# LED_INDICATORS.net
KiCad netlist of a schematic drawn in Altium Designer
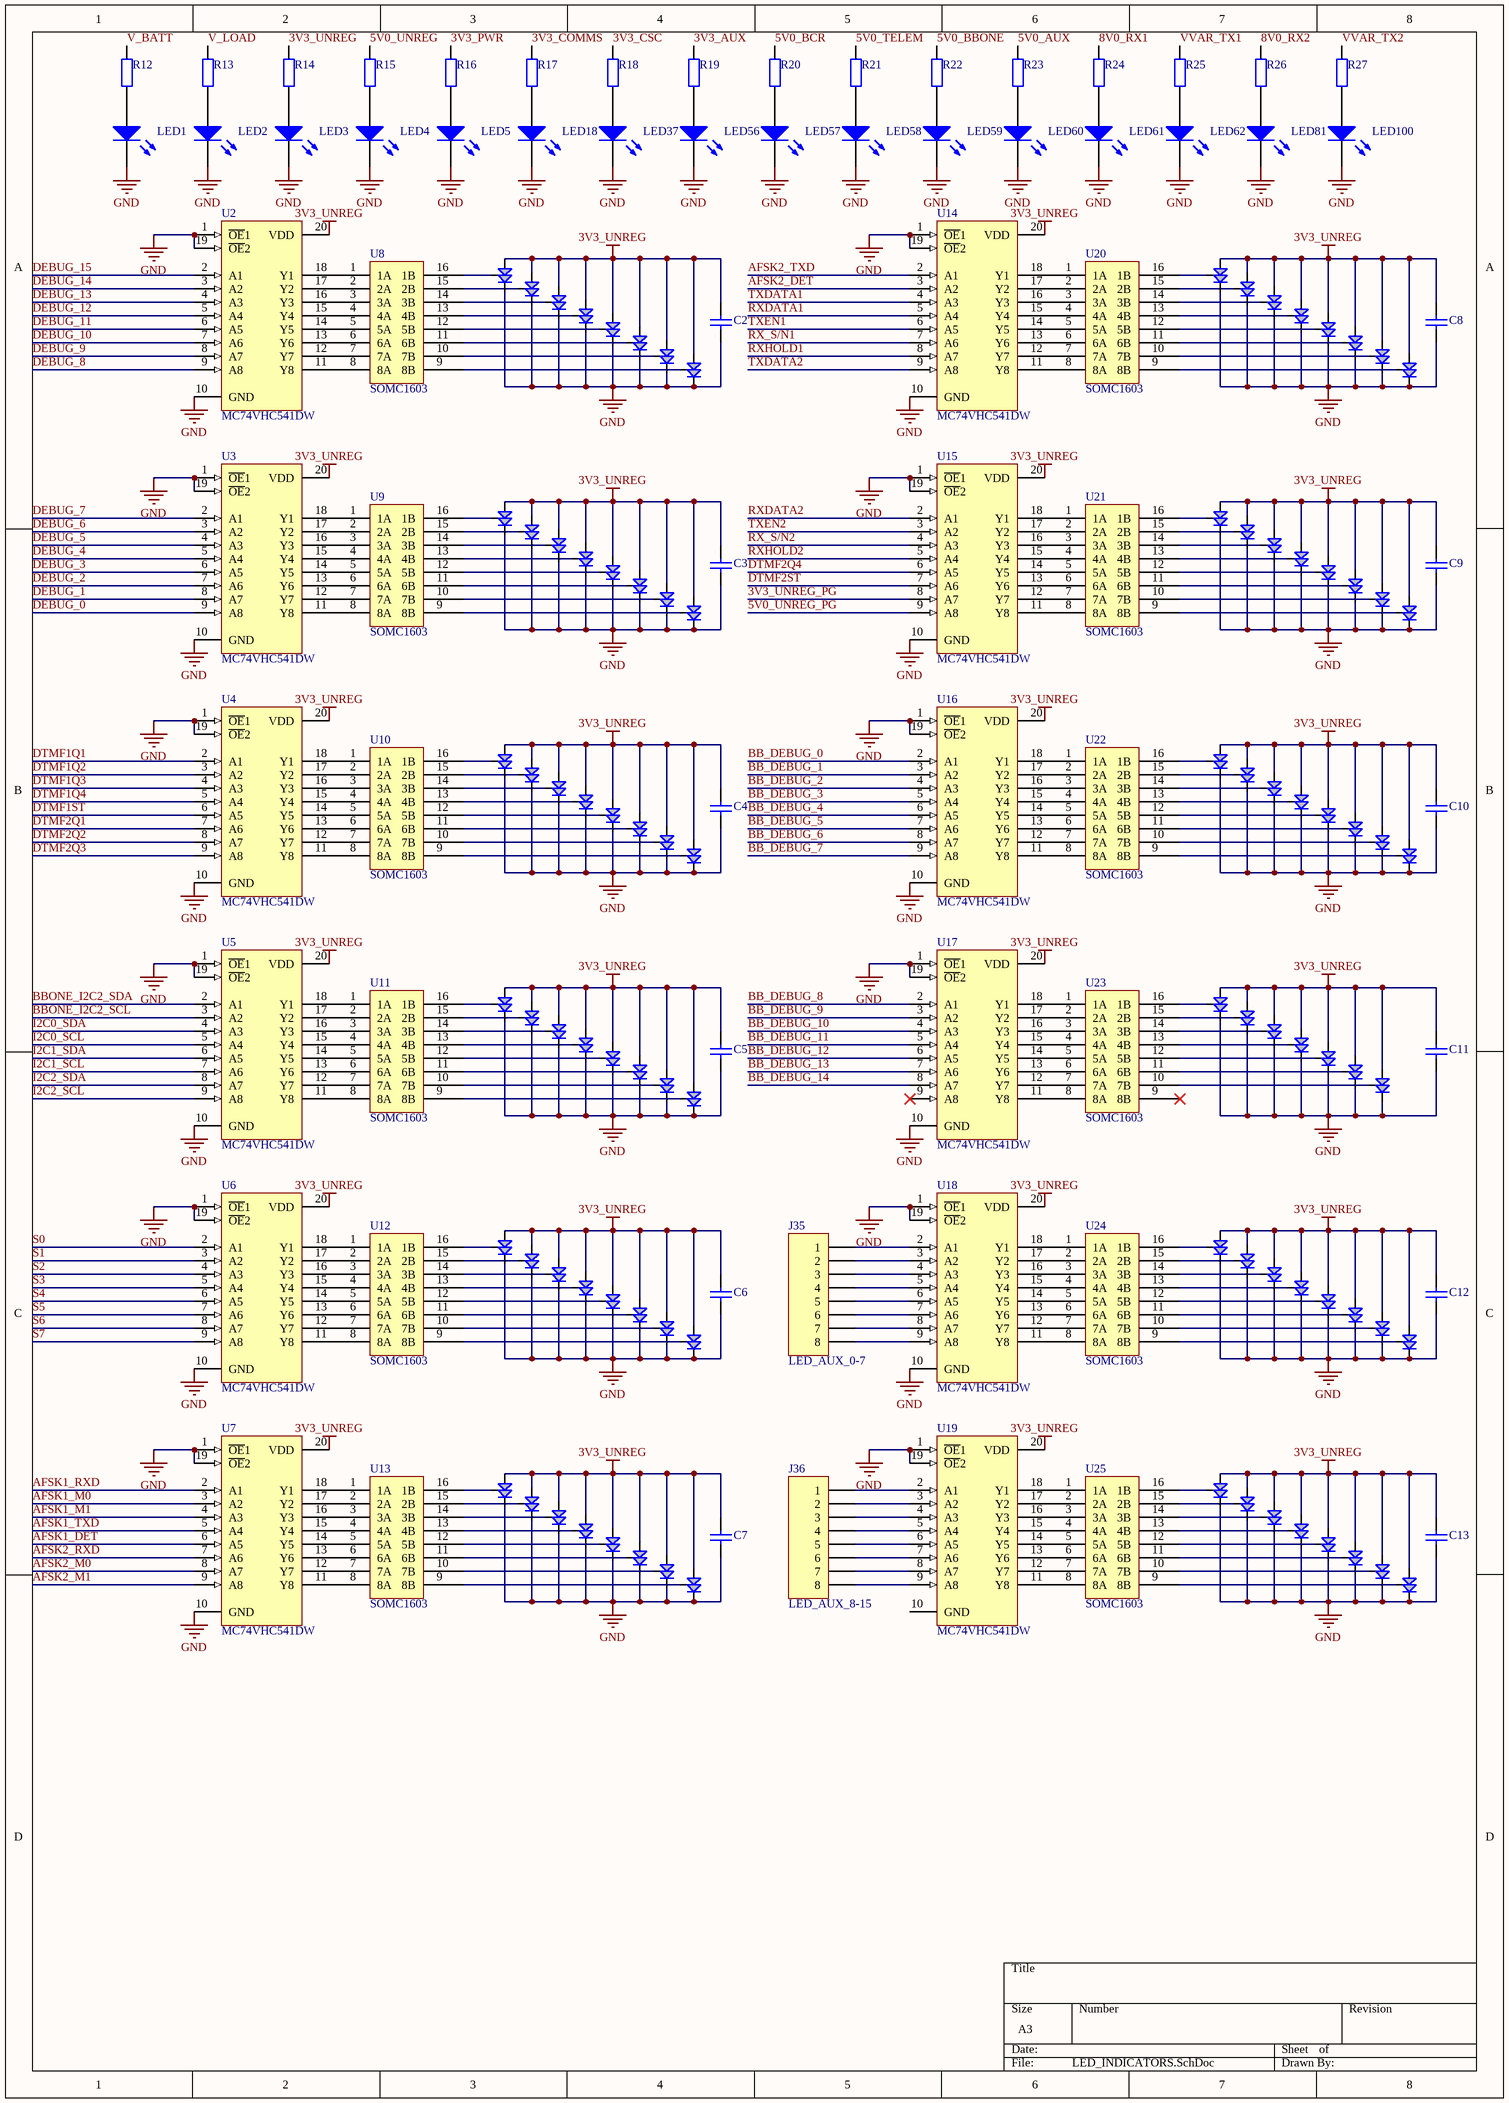
[diagram p0: LED_INDICATORS.SchDoc]

(export (version "E")
  (design (tool "Eeschema 10.0.6"))
  (components
    (comp (ref "C2")
      (value "~")
      (footprint "6-0805_M")
      (description "Capacitor")
      (fields (field (name "PUBLISHER") "Altium Limited"))
      (libsource (lib "Miscellaneous Devices") (part "Cap"))
    )
    (comp (ref "C3")
      (value "~")
      (footprint "6-0805_M")
      (description "Capacitor")
      (fields (field (name "PUBLISHER") "Altium Limited"))
      (libsource (lib "Miscellaneous Devices") (part "Cap"))
    )
    (comp (ref "C4")
      (value "~")
      (footprint "6-0805_M")
      (description "Capacitor")
      (fields (field (name "PUBLISHER") "Altium Limited"))
      (libsource (lib "Miscellaneous Devices") (part "Cap"))
    )
    (comp (ref "C5")
      (value "~")
      (footprint "6-0805_M")
      (description "Capacitor")
      (fields (field (name "PUBLISHER") "Altium Limited"))
      (libsource (lib "Miscellaneous Devices") (part "Cap"))
    )
    (comp (ref "C6")
      (value "~")
      (footprint "6-0805_M")
      (description "Capacitor")
      (fields (field (name "PUBLISHER") "Altium Limited"))
      (libsource (lib "Miscellaneous Devices") (part "Cap"))
    )
    (comp (ref "C7")
      (value "~")
      (footprint "6-0805_M")
      (description "Capacitor")
      (fields (field (name "PUBLISHER") "Altium Limited"))
      (libsource (lib "Miscellaneous Devices") (part "Cap"))
    )
    (comp (ref "C8")
      (value "~")
      (footprint "6-0805_M")
      (description "Capacitor")
      (fields (field (name "PUBLISHER") "Altium Limited"))
      (libsource (lib "Miscellaneous Devices") (part "Cap"))
    )
    (comp (ref "C9")
      (value "~")
      (footprint "6-0805_M")
      (description "Capacitor")
      (fields (field (name "PUBLISHER") "Altium Limited"))
      (libsource (lib "Miscellaneous Devices") (part "Cap"))
    )
    (comp (ref "C10")
      (value "~")
      (footprint "6-0805_M")
      (description "Capacitor")
      (fields (field (name "PUBLISHER") "Altium Limited"))
      (libsource (lib "Miscellaneous Devices") (part "Cap"))
    )
    (comp (ref "C11")
      (value "~")
      (footprint "6-0805_M")
      (description "Capacitor")
      (fields (field (name "PUBLISHER") "Altium Limited"))
      (libsource (lib "Miscellaneous Devices") (part "Cap"))
    )
    (comp (ref "C12")
      (value "~")
      (footprint "6-0805_M")
      (description "Capacitor")
      (fields (field (name "PUBLISHER") "Altium Limited"))
      (libsource (lib "Miscellaneous Devices") (part "Cap"))
    )
    (comp (ref "C13")
      (value "~")
      (footprint "6-0805_M")
      (description "Capacitor")
      (fields (field (name "PUBLISHER") "Altium Limited"))
      (libsource (lib "Miscellaneous Devices") (part "Cap"))
    )
    (comp (ref "J35")
      (value "LED_AUX_0-7")
      (footprint "HDR1X8")
      (description "Header, 8-Pin")
      (fields (field (name "PUBLISHER") "Altium Limited"))
      (libsource (lib "Miscellaneous Connectors") (part "Header 8"))
    )
    (comp (ref "J36")
      (value "LED_AUX_8-15")
      (footprint "HDR1X8")
      (description "Header, 8-Pin")
      (fields (field (name "PUBLISHER") "Altium Limited"))
      (libsource (lib "Miscellaneous Connectors") (part "Header 8"))
    )
    (comp (ref "LED1")
      (value "V_BATT")
      (footprint "6-0805_M")
      (description "Typical INFRARED GaAs LED")
      (fields (field (name "PUBLISHER") "Altium Limited"))
      (libsource (lib "Miscellaneous Devices") (part "LED0"))
    )
    (comp (ref "LED2")
      (value "V_LOAD")
      (footprint "6-0805_M")
      (description "Typical INFRARED GaAs LED")
      (fields (field (name "PUBLISHER") "Altium Limited"))
      (libsource (lib "Miscellaneous Devices") (part "LED0"))
    )
    (comp (ref "LED3")
      (value "3V3_UNREG")
      (footprint "6-0805_M")
      (description "Typical INFRARED GaAs LED")
      (fields (field (name "PUBLISHER") "Altium Limited"))
      (libsource (lib "Miscellaneous Devices") (part "LED0"))
    )
    (comp (ref "LED4")
      (value "5V0_UNREG")
      (footprint "6-0805_M")
      (description "Typical INFRARED GaAs LED")
      (fields (field (name "PUBLISHER") "Altium Limited"))
      (libsource (lib "Miscellaneous Devices") (part "LED0"))
    )
    (comp (ref "LED5")
      (value "3V3_PWR")
      (footprint "6-0805_M")
      (description "Typical INFRARED GaAs LED")
      (fields (field (name "PUBLISHER") "Altium Limited"))
      (libsource (lib "Miscellaneous Devices") (part "LED0"))
    )
    (comp (ref "LED6")
      (value "DEBUG_15")
      (footprint "BIDIRECTIONAL LED")
      (libsource (lib "FlatBoards") (part "BIDIRECTIONAL LED"))
    )
    (comp (ref "LED7")
      (value "DEBUG_7")
      (footprint "BIDIRECTIONAL LED")
      (libsource (lib "FlatBoards") (part "BIDIRECTIONAL LED"))
    )
    (comp (ref "LED8")
      (value "DTMF1Q1")
      (footprint "BIDIRECTIONAL LED")
      (libsource (lib "FlatBoards") (part "BIDIRECTIONAL LED"))
    )
    (comp (ref "LED9")
      (value "DTMF2Q4")
      (footprint "BIDIRECTIONAL LED")
      (libsource (lib "FlatBoards") (part "BIDIRECTIONAL LED"))
    )
    (comp (ref "LED10")
      (value "S0")
      (footprint "BIDIRECTIONAL LED")
      (libsource (lib "FlatBoards") (part "BIDIRECTIONAL LED"))
    )
    (comp (ref "LED11")
      (value "AFSK1_RXD")
      (footprint "BIDIRECTIONAL LED")
      (libsource (lib "FlatBoards") (part "BIDIRECTIONAL LED"))
    )
    (comp (ref "LED12")
      (value "DEBUG_14")
      (footprint "BIDIRECTIONAL LED")
      (libsource (lib "FlatBoards") (part "BIDIRECTIONAL LED"))
    )
    (comp (ref "LED13")
      (value "DEBUG_6")
      (footprint "BIDIRECTIONAL LED")
      (libsource (lib "FlatBoards") (part "BIDIRECTIONAL LED"))
    )
    (comp (ref "LED14")
      (value "DTMF1Q2")
      (footprint "BIDIRECTIONAL LED")
      (libsource (lib "FlatBoards") (part "BIDIRECTIONAL LED"))
    )
    (comp (ref "LED15")
      (value "DTMF2ST")
      (footprint "BIDIRECTIONAL LED")
      (libsource (lib "FlatBoards") (part "BIDIRECTIONAL LED"))
    )
    (comp (ref "LED16")
      (value "S1")
      (footprint "BIDIRECTIONAL LED")
      (libsource (lib "FlatBoards") (part "BIDIRECTIONAL LED"))
    )
    (comp (ref "LED17")
      (value "AFSK1_M0")
      (footprint "BIDIRECTIONAL LED")
      (libsource (lib "FlatBoards") (part "BIDIRECTIONAL LED"))
    )
    (comp (ref "LED18")
      (value "3V3_COMMS")
      (footprint "6-0805_M")
      (description "Typical INFRARED GaAs LED")
      (fields (field (name "PUBLISHER") "Altium Limited"))
      (libsource (lib "Miscellaneous Devices") (part "LED0"))
    )
    (comp (ref "LED19")
      (value "DEBUG_13")
      (footprint "BIDIRECTIONAL LED")
      (libsource (lib "FlatBoards") (part "BIDIRECTIONAL LED"))
    )
    (comp (ref "LED20")
      (value "DEBUG_5")
      (footprint "BIDIRECTIONAL LED")
      (libsource (lib "FlatBoards") (part "BIDIRECTIONAL LED"))
    )
    (comp (ref "LED21")
      (value "DTMF1Q3")
      (footprint "BIDIRECTIONAL LED")
      (libsource (lib "FlatBoards") (part "BIDIRECTIONAL LED"))
    )
    (comp (ref "LED22")
      (value "I2C0_SDA")
      (footprint "BIDIRECTIONAL LED")
      (libsource (lib "FlatBoards") (part "BIDIRECTIONAL LED"))
    )
    (comp (ref "LED23")
      (value "S2")
      (footprint "BIDIRECTIONAL LED")
      (libsource (lib "FlatBoards") (part "BIDIRECTIONAL LED"))
    )
    (comp (ref "LED24")
      (value "AFSK1_M1")
      (footprint "BIDIRECTIONAL LED")
      (libsource (lib "FlatBoards") (part "BIDIRECTIONAL LED"))
    )
    (comp (ref "LED25")
      (value "DEBUG_12")
      (footprint "BIDIRECTIONAL LED")
      (libsource (lib "FlatBoards") (part "BIDIRECTIONAL LED"))
    )
    (comp (ref "LED26")
      (value "DEBUG_4")
      (footprint "BIDIRECTIONAL LED")
      (libsource (lib "FlatBoards") (part "BIDIRECTIONAL LED"))
    )
    (comp (ref "LED27")
      (value "DTMF1Q4")
      (footprint "BIDIRECTIONAL LED")
      (libsource (lib "FlatBoards") (part "BIDIRECTIONAL LED"))
    )
    (comp (ref "LED28")
      (value "I2C0_SCL")
      (footprint "BIDIRECTIONAL LED")
      (libsource (lib "FlatBoards") (part "BIDIRECTIONAL LED"))
    )
    (comp (ref "LED29")
      (value "S3")
      (footprint "BIDIRECTIONAL LED")
      (libsource (lib "FlatBoards") (part "BIDIRECTIONAL LED"))
    )
    (comp (ref "LED30")
      (value "AFSK1_TXD")
      (footprint "BIDIRECTIONAL LED")
      (libsource (lib "FlatBoards") (part "BIDIRECTIONAL LED"))
    )
    (comp (ref "LED31")
      (value "DEBUG_11")
      (footprint "BIDIRECTIONAL LED")
      (libsource (lib "FlatBoards") (part "BIDIRECTIONAL LED"))
    )
    (comp (ref "LED32")
      (value "DEBUG_3")
      (footprint "BIDIRECTIONAL LED")
      (libsource (lib "FlatBoards") (part "BIDIRECTIONAL LED"))
    )
    (comp (ref "LED33")
      (value "DTMF1ST")
      (footprint "BIDIRECTIONAL LED")
      (libsource (lib "FlatBoards") (part "BIDIRECTIONAL LED"))
    )
    (comp (ref "LED34")
      (value "I2C1_SDA")
      (footprint "BIDIRECTIONAL LED")
      (libsource (lib "FlatBoards") (part "BIDIRECTIONAL LED"))
    )
    (comp (ref "LED35")
      (value "S4")
      (footprint "BIDIRECTIONAL LED")
      (libsource (lib "FlatBoards") (part "BIDIRECTIONAL LED"))
    )
    (comp (ref "LED36")
      (value "AFSK1_DET")
      (footprint "BIDIRECTIONAL LED")
      (libsource (lib "FlatBoards") (part "BIDIRECTIONAL LED"))
    )
    (comp (ref "LED37")
      (value "3V3_CSC")
      (footprint "6-0805_M")
      (description "Typical INFRARED GaAs LED")
      (fields (field (name "PUBLISHER") "Altium Limited"))
      (libsource (lib "Miscellaneous Devices") (part "LED0"))
    )
    (comp (ref "LED38")
      (value "DEBUG_10")
      (footprint "BIDIRECTIONAL LED")
      (libsource (lib "FlatBoards") (part "BIDIRECTIONAL LED"))
    )
    (comp (ref "LED39")
      (value "DEBUG_2")
      (footprint "BIDIRECTIONAL LED")
      (libsource (lib "FlatBoards") (part "BIDIRECTIONAL LED"))
    )
    (comp (ref "LED40")
      (value "DTMF2Q1")
      (footprint "BIDIRECTIONAL LED")
      (libsource (lib "FlatBoards") (part "BIDIRECTIONAL LED"))
    )
    (comp (ref "LED41")
      (value "I2C1_SCL")
      (footprint "BIDIRECTIONAL LED")
      (libsource (lib "FlatBoards") (part "BIDIRECTIONAL LED"))
    )
    (comp (ref "LED42")
      (value "S5")
      (footprint "BIDIRECTIONAL LED")
      (libsource (lib "FlatBoards") (part "BIDIRECTIONAL LED"))
    )
    (comp (ref "LED43")
      (value "AFSK2_RXD")
      (footprint "BIDIRECTIONAL LED")
      (libsource (lib "FlatBoards") (part "BIDIRECTIONAL LED"))
    )
    (comp (ref "LED44")
      (value "DEBUG_9")
      (footprint "BIDIRECTIONAL LED")
      (libsource (lib "FlatBoards") (part "BIDIRECTIONAL LED"))
    )
    (comp (ref "LED45")
      (value "DEBUG_1")
      (footprint "BIDIRECTIONAL LED")
      (libsource (lib "FlatBoards") (part "BIDIRECTIONAL LED"))
    )
    (comp (ref "LED46")
      (value "DTMF2Q2")
      (footprint "BIDIRECTIONAL LED")
      (libsource (lib "FlatBoards") (part "BIDIRECTIONAL LED"))
    )
    (comp (ref "LED47")
      (value "I2C2_SDA")
      (footprint "BIDIRECTIONAL LED")
      (libsource (lib "FlatBoards") (part "BIDIRECTIONAL LED"))
    )
    (comp (ref "LED48")
      (value "S6")
      (footprint "BIDIRECTIONAL LED")
      (libsource (lib "FlatBoards") (part "BIDIRECTIONAL LED"))
    )
    (comp (ref "LED49")
      (value "AFSK2_M0")
      (footprint "BIDIRECTIONAL LED")
      (libsource (lib "FlatBoards") (part "BIDIRECTIONAL LED"))
    )
    (comp (ref "LED50")
      (value "DEBUG_8")
      (footprint "BIDIRECTIONAL LED")
      (libsource (lib "FlatBoards") (part "BIDIRECTIONAL LED"))
    )
    (comp (ref "LED51")
      (value "DEBUG_0")
      (footprint "BIDIRECTIONAL LED")
      (libsource (lib "FlatBoards") (part "BIDIRECTIONAL LED"))
    )
    (comp (ref "LED52")
      (value "DTMF2Q3")
      (footprint "BIDIRECTIONAL LED")
      (libsource (lib "FlatBoards") (part "BIDIRECTIONAL LED"))
    )
    (comp (ref "LED53")
      (value "I2C2_SCL")
      (footprint "BIDIRECTIONAL LED")
      (libsource (lib "FlatBoards") (part "BIDIRECTIONAL LED"))
    )
    (comp (ref "LED54")
      (value "S7")
      (footprint "BIDIRECTIONAL LED")
      (libsource (lib "FlatBoards") (part "BIDIRECTIONAL LED"))
    )
    (comp (ref "LED55")
      (value "AFSK2_M1")
      (footprint "BIDIRECTIONAL LED")
      (libsource (lib "FlatBoards") (part "BIDIRECTIONAL LED"))
    )
    (comp (ref "LED56")
      (value "3V3_AUX")
      (footprint "6-0805_M")
      (description "Typical INFRARED GaAs LED")
      (fields (field (name "PUBLISHER") "Altium Limited"))
      (libsource (lib "Miscellaneous Devices") (part "LED0"))
    )
    (comp (ref "LED57")
      (value "5V0_BCR")
      (footprint "6-0805_M")
      (description "Typical INFRARED GaAs LED")
      (fields (field (name "PUBLISHER") "Altium Limited"))
      (libsource (lib "Miscellaneous Devices") (part "LED0"))
    )
    (comp (ref "LED58")
      (value "5V0_TELEM")
      (footprint "6-0805_M")
      (description "Typical INFRARED GaAs LED")
      (fields (field (name "PUBLISHER") "Altium Limited"))
      (libsource (lib "Miscellaneous Devices") (part "LED0"))
    )
    (comp (ref "LED59")
      (value "5V0_BBONE")
      (footprint "6-0805_M")
      (description "Typical INFRARED GaAs LED")
      (fields (field (name "PUBLISHER") "Altium Limited"))
      (libsource (lib "Miscellaneous Devices") (part "LED0"))
    )
    (comp (ref "LED60")
      (value "5V0_AUX")
      (footprint "6-0805_M")
      (description "Typical INFRARED GaAs LED")
      (fields (field (name "PUBLISHER") "Altium Limited"))
      (libsource (lib "Miscellaneous Devices") (part "LED0"))
    )
    (comp (ref "LED61")
      (value "8V0_RX1")
      (footprint "6-0805_M")
      (description "Typical INFRARED GaAs LED")
      (fields (field (name "PUBLISHER") "Altium Limited"))
      (libsource (lib "Miscellaneous Devices") (part "LED0"))
    )
    (comp (ref "LED62")
      (value "VVAR_TX1")
      (footprint "6-0805_M")
      (description "Typical INFRARED GaAs LED")
      (fields (field (name "PUBLISHER") "Altium Limited"))
      (libsource (lib "Miscellaneous Devices") (part "LED0"))
    )
    (comp (ref "LED63")
      (value "AFSK2_TXD")
      (footprint "BIDIRECTIONAL LED")
      (libsource (lib "FlatBoards") (part "BIDIRECTIONAL LED"))
    )
    (comp (ref "LED64")
      (value "RXDATA2")
      (footprint "BIDIRECTIONAL LED")
      (libsource (lib "FlatBoards") (part "BIDIRECTIONAL LED"))
    )
    (comp (ref "LED65")
      (value "BB_DEBUG_0")
      (footprint "BIDIRECTIONAL LED")
      (libsource (lib "FlatBoards") (part "BIDIRECTIONAL LED"))
    )
    (comp (ref "LED66")
      (value "BB_DEBUG_8")
      (footprint "BIDIRECTIONAL LED")
      (libsource (lib "FlatBoards") (part "BIDIRECTIONAL LED"))
    )
    (comp (ref "LED67")
      (value "LED_AUX_0")
      (footprint "BIDIRECTIONAL LED")
      (libsource (lib "FlatBoards") (part "BIDIRECTIONAL LED"))
    )
    (comp (ref "LED68")
      (value "LED_AUX_8")
      (footprint "BIDIRECTIONAL LED")
      (libsource (lib "FlatBoards") (part "BIDIRECTIONAL LED"))
    )
    (comp (ref "LED69")
      (value "AFSK2_DET")
      (footprint "BIDIRECTIONAL LED")
      (libsource (lib "FlatBoards") (part "BIDIRECTIONAL LED"))
    )
    (comp (ref "LED70")
      (value "TXEN2")
      (footprint "BIDIRECTIONAL LED")
      (libsource (lib "FlatBoards") (part "BIDIRECTIONAL LED"))
    )
    (comp (ref "LED71")
      (value "BB_DEBUG_1")
      (footprint "BIDIRECTIONAL LED")
      (libsource (lib "FlatBoards") (part "BIDIRECTIONAL LED"))
    )
    (comp (ref "LED72")
      (value "BB_DEBUG_9")
      (footprint "BIDIRECTIONAL LED")
      (libsource (lib "FlatBoards") (part "BIDIRECTIONAL LED"))
    )
    (comp (ref "LED73")
      (value "LED_AUX_1")
      (footprint "BIDIRECTIONAL LED")
      (libsource (lib "FlatBoards") (part "BIDIRECTIONAL LED"))
    )
    (comp (ref "LED74")
      (value "LED_AUX_9")
      (footprint "BIDIRECTIONAL LED")
      (libsource (lib "FlatBoards") (part "BIDIRECTIONAL LED"))
    )
    (comp (ref "LED75")
      (value "TXDATA1")
      (footprint "BIDIRECTIONAL LED")
      (libsource (lib "FlatBoards") (part "BIDIRECTIONAL LED"))
    )
    (comp (ref "LED76")
      (value "RX_S/N2")
      (footprint "BIDIRECTIONAL LED")
      (libsource (lib "FlatBoards") (part "BIDIRECTIONAL LED"))
    )
    (comp (ref "LED77")
      (value "BB_DEBUG_2")
      (footprint "BIDIRECTIONAL LED")
      (libsource (lib "FlatBoards") (part "BIDIRECTIONAL LED"))
    )
    (comp (ref "LED78")
      (value "BB_DEBUG_10")
      (footprint "BIDIRECTIONAL LED")
      (libsource (lib "FlatBoards") (part "BIDIRECTIONAL LED"))
    )
    (comp (ref "LED79")
      (value "LED_AUX_2")
      (footprint "BIDIRECTIONAL LED")
      (libsource (lib "FlatBoards") (part "BIDIRECTIONAL LED"))
    )
    (comp (ref "LED80")
      (value "LED_AUX_10")
      (footprint "BIDIRECTIONAL LED")
      (libsource (lib "FlatBoards") (part "BIDIRECTIONAL LED"))
    )
    (comp (ref "LED81")
      (value "8V0_RX2")
      (footprint "6-0805_M")
      (description "Typical INFRARED GaAs LED")
      (fields (field (name "PUBLISHER") "Altium Limited"))
      (libsource (lib "Miscellaneous Devices") (part "LED0"))
    )
    (comp (ref "LED82")
      (value "RXDATA1")
      (footprint "BIDIRECTIONAL LED")
      (libsource (lib "FlatBoards") (part "BIDIRECTIONAL LED"))
    )
    (comp (ref "LED83")
      (value "RXHOLD2")
      (footprint "BIDIRECTIONAL LED")
      (libsource (lib "FlatBoards") (part "BIDIRECTIONAL LED"))
    )
    (comp (ref "LED84")
      (value "BB_DEBUG_3")
      (footprint "BIDIRECTIONAL LED")
      (libsource (lib "FlatBoards") (part "BIDIRECTIONAL LED"))
    )
    (comp (ref "LED85")
      (value "BB_DEBUG_11")
      (footprint "BIDIRECTIONAL LED")
      (libsource (lib "FlatBoards") (part "BIDIRECTIONAL LED"))
    )
    (comp (ref "LED86")
      (value "LED_AUX_3")
      (footprint "BIDIRECTIONAL LED")
      (libsource (lib "FlatBoards") (part "BIDIRECTIONAL LED"))
    )
    (comp (ref "LED87")
      (value "LED_AUX_11")
      (footprint "BIDIRECTIONAL LED")
      (libsource (lib "FlatBoards") (part "BIDIRECTIONAL LED"))
    )
    (comp (ref "LED88")
      (value "TXEN1")
      (footprint "BIDIRECTIONAL LED")
      (libsource (lib "FlatBoards") (part "BIDIRECTIONAL LED"))
    )
    (comp (ref "LED89")
      (value "BBONE_I2C2_SDA")
      (footprint "BIDIRECTIONAL LED")
      (libsource (lib "FlatBoards") (part "BIDIRECTIONAL LED"))
    )
    (comp (ref "LED90")
      (value "BB_DEBUG_4")
      (footprint "BIDIRECTIONAL LED")
      (libsource (lib "FlatBoards") (part "BIDIRECTIONAL LED"))
    )
    (comp (ref "LED91")
      (value "BB_DEBUG_12")
      (footprint "BIDIRECTIONAL LED")
      (libsource (lib "FlatBoards") (part "BIDIRECTIONAL LED"))
    )
    (comp (ref "LED92")
      (value "LED_AUX_4")
      (footprint "BIDIRECTIONAL LED")
      (libsource (lib "FlatBoards") (part "BIDIRECTIONAL LED"))
    )
    (comp (ref "LED93")
      (value "LED_AUX_12")
      (footprint "BIDIRECTIONAL LED")
      (libsource (lib "FlatBoards") (part "BIDIRECTIONAL LED"))
    )
    (comp (ref "LED94")
      (value "RX_S/N1")
      (footprint "BIDIRECTIONAL LED")
      (libsource (lib "FlatBoards") (part "BIDIRECTIONAL LED"))
    )
    (comp (ref "LED95")
      (value "BBONE_I2C2_SCL")
      (footprint "BIDIRECTIONAL LED")
      (libsource (lib "FlatBoards") (part "BIDIRECTIONAL LED"))
    )
    (comp (ref "LED96")
      (value "BB_DEBUG_5")
      (footprint "BIDIRECTIONAL LED")
      (libsource (lib "FlatBoards") (part "BIDIRECTIONAL LED"))
    )
    (comp (ref "LED97")
      (value "BB_DEBUG_13")
      (footprint "BIDIRECTIONAL LED")
      (libsource (lib "FlatBoards") (part "BIDIRECTIONAL LED"))
    )
    (comp (ref "LED98")
      (value "LED_AUX_5")
      (footprint "BIDIRECTIONAL LED")
      (libsource (lib "FlatBoards") (part "BIDIRECTIONAL LED"))
    )
    (comp (ref "LED99")
      (value "LED_AUX_13")
      (footprint "BIDIRECTIONAL LED")
      (libsource (lib "FlatBoards") (part "BIDIRECTIONAL LED"))
    )
    (comp (ref "LED100")
      (value "VVAR_TX2")
      (footprint "6-0805_M")
      (description "Typical INFRARED GaAs LED")
      (fields (field (name "PUBLISHER") "Altium Limited"))
      (libsource (lib "Miscellaneous Devices") (part "LED0"))
    )
    (comp (ref "LED101")
      (value "RXHOLD1")
      (footprint "BIDIRECTIONAL LED")
      (libsource (lib "FlatBoards") (part "BIDIRECTIONAL LED"))
    )
    (comp (ref "LED102")
      (value "3V3_UNREG_PG")
      (footprint "BIDIRECTIONAL LED")
      (libsource (lib "FlatBoards") (part "BIDIRECTIONAL LED"))
    )
    (comp (ref "LED103")
      (value "BB_DEBUG_6")
      (footprint "BIDIRECTIONAL LED")
      (libsource (lib "FlatBoards") (part "BIDIRECTIONAL LED"))
    )
    (comp (ref "LED104")
      (value "BB_DEBUG_14")
      (footprint "BIDIRECTIONAL LED")
      (libsource (lib "FlatBoards") (part "BIDIRECTIONAL LED"))
    )
    (comp (ref "LED105")
      (value "LED_AUX_6")
      (footprint "BIDIRECTIONAL LED")
      (libsource (lib "FlatBoards") (part "BIDIRECTIONAL LED"))
    )
    (comp (ref "LED106")
      (value "LED_AUX_14")
      (footprint "BIDIRECTIONAL LED")
      (libsource (lib "FlatBoards") (part "BIDIRECTIONAL LED"))
    )
    (comp (ref "LED107")
      (value "TXDATA2")
      (footprint "BIDIRECTIONAL LED")
      (libsource (lib "FlatBoards") (part "BIDIRECTIONAL LED"))
    )
    (comp (ref "LED108")
      (value "5V0_UNREG_PG")
      (footprint "BIDIRECTIONAL LED")
      (libsource (lib "FlatBoards") (part "BIDIRECTIONAL LED"))
    )
    (comp (ref "LED109")
      (value "BB_DEBUG_7")
      (footprint "BIDIRECTIONAL LED")
      (libsource (lib "FlatBoards") (part "BIDIRECTIONAL LED"))
    )
    (comp (ref "LED111")
      (value "LED_AUX_7")
      (footprint "BIDIRECTIONAL LED")
      (libsource (lib "FlatBoards") (part "BIDIRECTIONAL LED"))
    )
    (comp (ref "LED112")
      (value "LED_AUX_15")
      (footprint "BIDIRECTIONAL LED")
      (libsource (lib "FlatBoards") (part "BIDIRECTIONAL LED"))
    )
    (comp (ref "R12")
      (value "Res2")
      (footprint "6-0805_M")
      (description "Resistor")
      (fields (field (name "PUBLISHER") "Altium Limited"))
      (libsource (lib "Miscellaneous Devices") (part "Res2"))
    )
    (comp (ref "R13")
      (value "Res2")
      (footprint "6-0805_M")
      (description "Resistor")
      (fields (field (name "PUBLISHER") "Altium Limited"))
      (libsource (lib "Miscellaneous Devices") (part "Res2"))
    )
    (comp (ref "R14")
      (value "Res2")
      (footprint "6-0805_M")
      (description "Resistor")
      (fields (field (name "PUBLISHER") "Altium Limited"))
      (libsource (lib "Miscellaneous Devices") (part "Res2"))
    )
    (comp (ref "R15")
      (value "Res2")
      (footprint "6-0805_M")
      (description "Resistor")
      (fields (field (name "PUBLISHER") "Altium Limited"))
      (libsource (lib "Miscellaneous Devices") (part "Res2"))
    )
    (comp (ref "R16")
      (value "Res2")
      (footprint "6-0805_M")
      (description "Resistor")
      (fields (field (name "PUBLISHER") "Altium Limited"))
      (libsource (lib "Miscellaneous Devices") (part "Res2"))
    )
    (comp (ref "R17")
      (value "Res2")
      (footprint "6-0805_M")
      (description "Resistor")
      (fields (field (name "PUBLISHER") "Altium Limited"))
      (libsource (lib "Miscellaneous Devices") (part "Res2"))
    )
    (comp (ref "R18")
      (value "Res2")
      (footprint "6-0805_M")
      (description "Resistor")
      (fields (field (name "PUBLISHER") "Altium Limited"))
      (libsource (lib "Miscellaneous Devices") (part "Res2"))
    )
    (comp (ref "R19")
      (value "Res2")
      (footprint "6-0805_M")
      (description "Resistor")
      (fields (field (name "PUBLISHER") "Altium Limited"))
      (libsource (lib "Miscellaneous Devices") (part "Res2"))
    )
    (comp (ref "R20")
      (value "Res2")
      (footprint "6-0805_M")
      (description "Resistor")
      (fields (field (name "PUBLISHER") "Altium Limited"))
      (libsource (lib "Miscellaneous Devices") (part "Res2"))
    )
    (comp (ref "R21")
      (value "Res2")
      (footprint "6-0805_M")
      (description "Resistor")
      (fields (field (name "PUBLISHER") "Altium Limited"))
      (libsource (lib "Miscellaneous Devices") (part "Res2"))
    )
    (comp (ref "R22")
      (value "Res2")
      (footprint "6-0805_M")
      (description "Resistor")
      (fields (field (name "PUBLISHER") "Altium Limited"))
      (libsource (lib "Miscellaneous Devices") (part "Res2"))
    )
    (comp (ref "R23")
      (value "Res2")
      (footprint "6-0805_M")
      (description "Resistor")
      (fields (field (name "PUBLISHER") "Altium Limited"))
      (libsource (lib "Miscellaneous Devices") (part "Res2"))
    )
    (comp (ref "R24")
      (value "Res2")
      (footprint "6-0805_M")
      (description "Resistor")
      (fields (field (name "PUBLISHER") "Altium Limited"))
      (libsource (lib "Miscellaneous Devices") (part "Res2"))
    )
    (comp (ref "R25")
      (value "Res2")
      (footprint "6-0805_M")
      (description "Resistor")
      (fields (field (name "PUBLISHER") "Altium Limited"))
      (libsource (lib "Miscellaneous Devices") (part "Res2"))
    )
    (comp (ref "R26")
      (value "Res2")
      (footprint "6-0805_M")
      (description "Resistor")
      (fields (field (name "PUBLISHER") "Altium Limited"))
      (libsource (lib "Miscellaneous Devices") (part "Res2"))
    )
    (comp (ref "R27")
      (value "Res2")
      (footprint "6-0805_M")
      (description "Resistor")
      (fields (field (name "PUBLISHER") "Altium Limited"))
      (libsource (lib "Miscellaneous Devices") (part "Res2"))
    )
    (comp (ref "U2")
      (value "MC74VHC541DW")
      (footprint "751D-04_M")
      (description "Octal Bus Buffer")
      (fields (field (name "PUBLISHER") "Altium Limited"))
      (libsource (lib "FlatBoards") (part "MC74VHC541DW"))
    )
    (comp (ref "U3")
      (value "MC74VHC541DW")
      (footprint "751D-04_M")
      (description "Octal Bus Buffer")
      (fields (field (name "PUBLISHER") "Altium Limited"))
      (libsource (lib "FlatBoards") (part "MC74VHC541DW"))
    )
    (comp (ref "U4")
      (value "MC74VHC541DW")
      (footprint "751D-04_M")
      (description "Octal Bus Buffer")
      (fields (field (name "PUBLISHER") "Altium Limited"))
      (libsource (lib "FlatBoards") (part "MC74VHC541DW"))
    )
    (comp (ref "U5")
      (value "MC74VHC541DW")
      (footprint "751D-04_M")
      (description "Octal Bus Buffer")
      (fields (field (name "PUBLISHER") "Altium Limited"))
      (libsource (lib "FlatBoards") (part "MC74VHC541DW"))
    )
    (comp (ref "U6")
      (value "MC74VHC541DW")
      (footprint "751D-04_M")
      (description "Octal Bus Buffer")
      (fields (field (name "PUBLISHER") "Altium Limited"))
      (libsource (lib "FlatBoards") (part "MC74VHC541DW"))
    )
    (comp (ref "U7")
      (value "MC74VHC541DW")
      (footprint "751D-04_M")
      (description "Octal Bus Buffer")
      (fields (field (name "PUBLISHER") "Altium Limited"))
      (libsource (lib "FlatBoards") (part "MC74VHC541DW"))
    )
    (comp (ref "U8")
      (value "SOMC1603")
      (footprint "SOMC1603")
      (libsource (lib "FlatBoards") (part "SOMC1603"))
    )
    (comp (ref "U9")
      (value "SOMC1603")
      (footprint "SOMC1603")
      (libsource (lib "FlatBoards") (part "SOMC1603"))
    )
    (comp (ref "U10")
      (value "SOMC1603")
      (footprint "SOMC1603")
      (libsource (lib "FlatBoards") (part "SOMC1603"))
    )
    (comp (ref "U11")
      (value "SOMC1603")
      (footprint "SOMC1603")
      (libsource (lib "FlatBoards") (part "SOMC1603"))
    )
    (comp (ref "U12")
      (value "SOMC1603")
      (footprint "SOMC1603")
      (libsource (lib "FlatBoards") (part "SOMC1603"))
    )
    (comp (ref "U13")
      (value "SOMC1603")
      (footprint "SOMC1603")
      (libsource (lib "FlatBoards") (part "SOMC1603"))
    )
    (comp (ref "U14")
      (value "MC74VHC541DW")
      (footprint "751D-04_M")
      (description "Octal Bus Buffer")
      (fields (field (name "PUBLISHER") "Altium Limited"))
      (libsource (lib "FlatBoards") (part "MC74VHC541DW"))
    )
    (comp (ref "U15")
      (value "MC74VHC541DW")
      (footprint "751D-04_M")
      (description "Octal Bus Buffer")
      (fields (field (name "PUBLISHER") "Altium Limited"))
      (libsource (lib "FlatBoards") (part "MC74VHC541DW"))
    )
    (comp (ref "U16")
      (value "MC74VHC541DW")
      (footprint "751D-04_M")
      (description "Octal Bus Buffer")
      (fields (field (name "PUBLISHER") "Altium Limited"))
      (libsource (lib "FlatBoards") (part "MC74VHC541DW"))
    )
    (comp (ref "U17")
      (value "MC74VHC541DW")
      (footprint "751D-04_M")
      (description "Octal Bus Buffer")
      (fields (field (name "PUBLISHER") "Altium Limited"))
      (libsource (lib "FlatBoards") (part "MC74VHC541DW"))
    )
    (comp (ref "U18")
      (value "MC74VHC541DW")
      (footprint "751D-04_M")
      (description "Octal Bus Buffer")
      (fields (field (name "PUBLISHER") "Altium Limited"))
      (libsource (lib "FlatBoards") (part "MC74VHC541DW"))
    )
    (comp (ref "U19")
      (value "MC74VHC541DW")
      (footprint "751D-04_M")
      (description "Octal Bus Buffer")
      (fields (field (name "PUBLISHER") "Altium Limited"))
      (libsource (lib "FlatBoards") (part "MC74VHC541DW"))
    )
    (comp (ref "U20")
      (value "SOMC1603")
      (footprint "SOMC1603")
      (libsource (lib "FlatBoards") (part "SOMC1603"))
    )
    (comp (ref "U21")
      (value "SOMC1603")
      (footprint "SOMC1603")
      (libsource (lib "FlatBoards") (part "SOMC1603"))
    )
    (comp (ref "U22")
      (value "SOMC1603")
      (footprint "SOMC1603")
      (libsource (lib "FlatBoards") (part "SOMC1603"))
    )
    (comp (ref "U23")
      (value "SOMC1603")
      (footprint "SOMC1603")
      (libsource (lib "FlatBoards") (part "SOMC1603"))
    )
    (comp (ref "U24")
      (value "SOMC1603")
      (footprint "SOMC1603")
      (libsource (lib "FlatBoards") (part "SOMC1603"))
    )
    (comp (ref "U25")
      (value "SOMC1603")
      (footprint "SOMC1603")
      (libsource (lib "FlatBoards") (part "SOMC1603"))
    )
  )
  (nets
    (net (code "1") (name "/3V3_AUX") (class "Default")
      (node (ref "R19") (pin "2") (pinfunction "2_2") (pintype "passive"))
    )
    (net (code "2") (name "/3V3_COMMS") (class "Default")
      (node (ref "R17") (pin "2") (pinfunction "2_2") (pintype "passive"))
    )
    (net (code "3") (name "/3V3_CSC") (class "Default")
      (node (ref "R18") (pin "2") (pinfunction "2_2") (pintype "passive"))
    )
    (net (code "4") (name "/3V3_PWR") (class "Default")
      (node (ref "R16") (pin "2") (pinfunction "2_2") (pintype "passive"))
    )
    (net (code "5") (name "/3V3_UNREG_PG") (class "Default")
      (node (ref "U15") (pin "8") (pinfunction "A7_8") (pintype "input"))
    )
    (net (code "6") (name "/5V0_AUX") (class "Default")
      (node (ref "R23") (pin "2") (pinfunction "2_2") (pintype "passive"))
    )
    (net (code "7") (name "/5V0_BBONE") (class "Default")
      (node (ref "R22") (pin "2") (pinfunction "2_2") (pintype "passive"))
    )
    (net (code "8") (name "/5V0_BCR") (class "Default")
      (node (ref "R20") (pin "2") (pinfunction "2_2") (pintype "passive"))
    )
    (net (code "9") (name "/5V0_TELEM") (class "Default")
      (node (ref "R21") (pin "2") (pinfunction "2_2") (pintype "passive"))
    )
    (net (code "10") (name "/5V0_UNREG") (class "Default")
      (node (ref "R15") (pin "2") (pinfunction "2_2") (pintype "passive"))
    )
    (net (code "11") (name "/5V0_UNREG_PG") (class "Default")
      (node (ref "U15") (pin "9") (pinfunction "A8_9") (pintype "input"))
    )
    (net (code "12") (name "/8V0_RX1") (class "Default")
      (node (ref "R24") (pin "2") (pinfunction "2_2") (pintype "passive"))
    )
    (net (code "13") (name "/8V0_RX2") (class "Default")
      (node (ref "R26") (pin "2") (pinfunction "2_2") (pintype "passive"))
    )
    (net (code "14") (name "/AFSK1_DET") (class "Default")
      (node (ref "U7") (pin "6") (pinfunction "A5_6") (pintype "input"))
    )
    (net (code "15") (name "/AFSK1_M0") (class "Default")
      (node (ref "U7") (pin "3") (pinfunction "A2_3") (pintype "input"))
    )
    (net (code "16") (name "/AFSK1_M1") (class "Default")
      (node (ref "U7") (pin "4") (pinfunction "A3_4") (pintype "input"))
    )
    (net (code "17") (name "/AFSK1_RXD") (class "Default")
      (node (ref "U7") (pin "2") (pinfunction "A1_2") (pintype "input"))
    )
    (net (code "18") (name "/AFSK1_TXD") (class "Default")
      (node (ref "U7") (pin "5") (pinfunction "A4_5") (pintype "input"))
    )
    (net (code "19") (name "/AFSK2_DET") (class "Default")
      (node (ref "U14") (pin "3") (pinfunction "A2_3") (pintype "input"))
    )
    (net (code "20") (name "/AFSK2_M0") (class "Default")
      (node (ref "U7") (pin "8") (pinfunction "A7_8") (pintype "input"))
    )
    (net (code "21") (name "/AFSK2_M1") (class "Default")
      (node (ref "U7") (pin "9") (pinfunction "A8_9") (pintype "input"))
    )
    (net (code "22") (name "/AFSK2_RXD") (class "Default")
      (node (ref "U7") (pin "7") (pinfunction "A6_7") (pintype "input"))
    )
    (net (code "23") (name "/AFSK2_TXD") (class "Default")
      (node (ref "U14") (pin "2") (pinfunction "A1_2") (pintype "input"))
    )
    (net (code "24") (name "/BBONE_I2C2_SCL") (class "Default")
      (node (ref "U5") (pin "3") (pinfunction "A2_3") (pintype "input"))
    )
    (net (code "25") (name "/BBONE_I2C2_SDA") (class "Default")
      (node (ref "U5") (pin "2") (pinfunction "A1_2") (pintype "input"))
    )
    (net (code "26") (name "/BB_DEBUG_0") (class "Default")
      (node (ref "U16") (pin "2") (pinfunction "A1_2") (pintype "input"))
    )
    (net (code "27") (name "/BB_DEBUG_1") (class "Default")
      (node (ref "U16") (pin "3") (pinfunction "A2_3") (pintype "input"))
    )
    (net (code "28") (name "/BB_DEBUG_2") (class "Default")
      (node (ref "U16") (pin "4") (pinfunction "A3_4") (pintype "input"))
    )
    (net (code "29") (name "/BB_DEBUG_3") (class "Default")
      (node (ref "U16") (pin "5") (pinfunction "A4_5") (pintype "input"))
    )
    (net (code "30") (name "/BB_DEBUG_4") (class "Default")
      (node (ref "U16") (pin "6") (pinfunction "A5_6") (pintype "input"))
    )
    (net (code "31") (name "/BB_DEBUG_5") (class "Default")
      (node (ref "U16") (pin "7") (pinfunction "A6_7") (pintype "input"))
    )
    (net (code "32") (name "/BB_DEBUG_6") (class "Default")
      (node (ref "U16") (pin "8") (pinfunction "A7_8") (pintype "input"))
    )
    (net (code "33") (name "/BB_DEBUG_7") (class "Default")
      (node (ref "U16") (pin "9") (pinfunction "A8_9") (pintype "input"))
    )
    (net (code "34") (name "/BB_DEBUG_8") (class "Default")
      (node (ref "U17") (pin "2") (pinfunction "A1_2") (pintype "input"))
    )
    (net (code "35") (name "/BB_DEBUG_9") (class "Default")
      (node (ref "U17") (pin "3") (pinfunction "A2_3") (pintype "input"))
    )
    (net (code "36") (name "/BB_DEBUG_10") (class "Default")
      (node (ref "U17") (pin "4") (pinfunction "A3_4") (pintype "input"))
    )
    (net (code "37") (name "/BB_DEBUG_11") (class "Default")
      (node (ref "U17") (pin "5") (pinfunction "A4_5") (pintype "input"))
    )
    (net (code "38") (name "/BB_DEBUG_12") (class "Default")
      (node (ref "U17") (pin "6") (pinfunction "A5_6") (pintype "input"))
    )
    (net (code "39") (name "/BB_DEBUG_13") (class "Default")
      (node (ref "U17") (pin "7") (pinfunction "A6_7") (pintype "input"))
    )
    (net (code "40") (name "/BB_DEBUG_14") (class "Default")
      (node (ref "U17") (pin "8") (pinfunction "A7_8") (pintype "input"))
    )
    (net (code "41") (name "/DEBUG_0") (class "Default")
      (node (ref "U3") (pin "9") (pinfunction "A8_9") (pintype "input"))
    )
    (net (code "42") (name "/DEBUG_1") (class "Default")
      (node (ref "U3") (pin "8") (pinfunction "A7_8") (pintype "input"))
    )
    (net (code "43") (name "/DEBUG_2") (class "Default")
      (node (ref "U3") (pin "7") (pinfunction "A6_7") (pintype "input"))
    )
    (net (code "44") (name "/DEBUG_3") (class "Default")
      (node (ref "U3") (pin "6") (pinfunction "A5_6") (pintype "input"))
    )
    (net (code "45") (name "/DEBUG_4") (class "Default")
      (node (ref "U3") (pin "5") (pinfunction "A4_5") (pintype "input"))
    )
    (net (code "46") (name "/DEBUG_5") (class "Default")
      (node (ref "U3") (pin "4") (pinfunction "A3_4") (pintype "input"))
    )
    (net (code "47") (name "/DEBUG_6") (class "Default")
      (node (ref "U3") (pin "3") (pinfunction "A2_3") (pintype "input"))
    )
    (net (code "48") (name "/DEBUG_7") (class "Default")
      (node (ref "U3") (pin "2") (pinfunction "A1_2") (pintype "input"))
    )
    (net (code "49") (name "/DEBUG_8") (class "Default")
      (node (ref "U2") (pin "9") (pinfunction "A8_9") (pintype "input"))
    )
    (net (code "50") (name "/DEBUG_9") (class "Default")
      (node (ref "U2") (pin "8") (pinfunction "A7_8") (pintype "input"))
    )
    (net (code "51") (name "/DEBUG_10") (class "Default")
      (node (ref "U2") (pin "7") (pinfunction "A6_7") (pintype "input"))
    )
    (net (code "52") (name "/DEBUG_11") (class "Default")
      (node (ref "U2") (pin "6") (pinfunction "A5_6") (pintype "input"))
    )
    (net (code "53") (name "/DEBUG_12") (class "Default")
      (node (ref "U2") (pin "5") (pinfunction "A4_5") (pintype "input"))
    )
    (net (code "54") (name "/DEBUG_13") (class "Default")
      (node (ref "U2") (pin "4") (pinfunction "A3_4") (pintype "input"))
    )
    (net (code "55") (name "/DEBUG_14") (class "Default")
      (node (ref "U2") (pin "3") (pinfunction "A2_3") (pintype "input"))
    )
    (net (code "56") (name "/DEBUG_15") (class "Default")
      (node (ref "U2") (pin "2") (pinfunction "A1_2") (pintype "input"))
    )
    (net (code "57") (name "/DTMF1Q1") (class "Default")
      (node (ref "U4") (pin "2") (pinfunction "A1_2") (pintype "input"))
    )
    (net (code "58") (name "/DTMF1Q2") (class "Default")
      (node (ref "U4") (pin "3") (pinfunction "A2_3") (pintype "input"))
    )
    (net (code "59") (name "/DTMF1Q3") (class "Default")
      (node (ref "U4") (pin "4") (pinfunction "A3_4") (pintype "input"))
    )
    (net (code "60") (name "/DTMF1Q4") (class "Default")
      (node (ref "U4") (pin "5") (pinfunction "A4_5") (pintype "input"))
    )
    (net (code "61") (name "/DTMF1ST") (class "Default")
      (node (ref "U4") (pin "6") (pinfunction "A5_6") (pintype "input"))
    )
    (net (code "62") (name "/DTMF2Q1") (class "Default")
      (node (ref "U4") (pin "7") (pinfunction "A6_7") (pintype "input"))
    )
    (net (code "63") (name "/DTMF2Q2") (class "Default")
      (node (ref "U4") (pin "8") (pinfunction "A7_8") (pintype "input"))
    )
    (net (code "64") (name "/DTMF2Q3") (class "Default")
      (node (ref "U4") (pin "9") (pinfunction "A8_9") (pintype "input"))
    )
    (net (code "65") (name "/DTMF2Q4") (class "Default")
      (node (ref "U15") (pin "6") (pinfunction "A5_6") (pintype "input"))
    )
    (net (code "66") (name "/DTMF2ST") (class "Default")
      (node (ref "U15") (pin "7") (pinfunction "A6_7") (pintype "input"))
    )
    (net (code "67") (name "/I2C0_SCL") (class "Default")
      (node (ref "U5") (pin "5") (pinfunction "A4_5") (pintype "input"))
    )
    (net (code "68") (name "/I2C0_SDA") (class "Default")
      (node (ref "U5") (pin "4") (pinfunction "A3_4") (pintype "input"))
    )
    (net (code "69") (name "/I2C1_SCL") (class "Default")
      (node (ref "U5") (pin "7") (pinfunction "A6_7") (pintype "input"))
    )
    (net (code "70") (name "/I2C1_SDA") (class "Default")
      (node (ref "U5") (pin "6") (pinfunction "A5_6") (pintype "input"))
    )
    (net (code "71") (name "/I2C2_SCL") (class "Default")
      (node (ref "U5") (pin "9") (pinfunction "A8_9") (pintype "input"))
    )
    (net (code "72") (name "/I2C2_SDA") (class "Default")
      (node (ref "U5") (pin "8") (pinfunction "A7_8") (pintype "input"))
    )
    (net (code "73") (name "/RXDATA1") (class "Default")
      (node (ref "U14") (pin "5") (pinfunction "A4_5") (pintype "input"))
    )
    (net (code "74") (name "/RXDATA2") (class "Default")
      (node (ref "U15") (pin "2") (pinfunction "A1_2") (pintype "input"))
    )
    (net (code "75") (name "/RXHOLD1") (class "Default")
      (node (ref "U14") (pin "8") (pinfunction "A7_8") (pintype "input"))
    )
    (net (code "76") (name "/RXHOLD2") (class "Default")
      (node (ref "U15") (pin "5") (pinfunction "A4_5") (pintype "input"))
    )
    (net (code "77") (name "/RX_S{slash}N1") (class "Default")
      (node (ref "U14") (pin "7") (pinfunction "A6_7") (pintype "input"))
    )
    (net (code "78") (name "/RX_S{slash}N2") (class "Default")
      (node (ref "U15") (pin "4") (pinfunction "A3_4") (pintype "input"))
    )
    (net (code "79") (name "/S0") (class "Default")
      (node (ref "U6") (pin "2") (pinfunction "A1_2") (pintype "input"))
    )
    (net (code "80") (name "/S1") (class "Default")
      (node (ref "U6") (pin "3") (pinfunction "A2_3") (pintype "input"))
    )
    (net (code "81") (name "/S2") (class "Default")
      (node (ref "U6") (pin "4") (pinfunction "A3_4") (pintype "input"))
    )
    (net (code "82") (name "/S3") (class "Default")
      (node (ref "U6") (pin "5") (pinfunction "A4_5") (pintype "input"))
    )
    (net (code "83") (name "/S4") (class "Default")
      (node (ref "U6") (pin "6") (pinfunction "A5_6") (pintype "input"))
    )
    (net (code "84") (name "/S5") (class "Default")
      (node (ref "U6") (pin "7") (pinfunction "A6_7") (pintype "input"))
    )
    (net (code "85") (name "/S6") (class "Default")
      (node (ref "U6") (pin "8") (pinfunction "A7_8") (pintype "input"))
    )
    (net (code "86") (name "/S7") (class "Default")
      (node (ref "U6") (pin "9") (pinfunction "A8_9") (pintype "input"))
    )
    (net (code "87") (name "/TXDATA1") (class "Default")
      (node (ref "U14") (pin "4") (pinfunction "A3_4") (pintype "input"))
    )
    (net (code "88") (name "/TXDATA2") (class "Default")
      (node (ref "U14") (pin "9") (pinfunction "A8_9") (pintype "input"))
    )
    (net (code "89") (name "/TXEN1") (class "Default")
      (node (ref "U14") (pin "6") (pinfunction "A5_6") (pintype "input"))
    )
    (net (code "90") (name "/TXEN2") (class "Default")
      (node (ref "U15") (pin "3") (pinfunction "A2_3") (pintype "input"))
    )
    (net (code "91") (name "/VVAR_TX1") (class "Default")
      (node (ref "R25") (pin "2") (pinfunction "2_2") (pintype "passive"))
    )
    (net (code "92") (name "/VVAR_TX2") (class "Default")
      (node (ref "R27") (pin "2") (pinfunction "2_2") (pintype "passive"))
    )
    (net (code "93") (name "/V_BATT") (class "Default")
      (node (ref "R12") (pin "2") (pinfunction "2_2") (pintype "passive"))
    )
    (net (code "94") (name "/V_LOAD") (class "Default")
      (node (ref "R13") (pin "2") (pinfunction "2_2") (pintype "passive"))
    )
    (net (code "95") (name "3V3_UNREG") (class "Default")
      (node (ref "C10") (pin "2") (pinfunction "2_2") (pintype "passive"))
      (node (ref "C11") (pin "2") (pinfunction "2_2") (pintype "passive"))
      (node (ref "C12") (pin "2") (pinfunction "2_2") (pintype "passive"))
      (node (ref "C13") (pin "2") (pinfunction "2_2") (pintype "passive"))
      (node (ref "C2") (pin "2") (pinfunction "2_2") (pintype "passive"))
      (node (ref "C3") (pin "2") (pinfunction "2_2") (pintype "passive"))
      (node (ref "C4") (pin "2") (pinfunction "2_2") (pintype "passive"))
      (node (ref "C5") (pin "2") (pinfunction "2_2") (pintype "passive"))
      (node (ref "C6") (pin "2") (pinfunction "2_2") (pintype "passive"))
      (node (ref "C7") (pin "2") (pinfunction "2_2") (pintype "passive"))
      (node (ref "C8") (pin "2") (pinfunction "2_2") (pintype "passive"))
      (node (ref "C9") (pin "2") (pinfunction "2_2") (pintype "passive"))
      (node (ref "LED10") (pin "3") (pinfunction "VCC_3") (pintype "passive"))
      (node (ref "LED101") (pin "3") (pinfunction "VCC_3") (pintype "passive"))
      (node (ref "LED102") (pin "3") (pinfunction "VCC_3") (pintype "passive"))
      (node (ref "LED103") (pin "3") (pinfunction "VCC_3") (pintype "passive"))
      (node (ref "LED104") (pin "3") (pinfunction "VCC_3") (pintype "passive"))
      (node (ref "LED105") (pin "3") (pinfunction "VCC_3") (pintype "passive"))
      (node (ref "LED106") (pin "3") (pinfunction "VCC_3") (pintype "passive"))
      (node (ref "LED107") (pin "3") (pinfunction "VCC_3") (pintype "passive"))
      (node (ref "LED108") (pin "3") (pinfunction "VCC_3") (pintype "passive"))
      (node (ref "LED109") (pin "3") (pinfunction "VCC_3") (pintype "passive"))
      (node (ref "LED11") (pin "3") (pinfunction "VCC_3") (pintype "passive"))
      (node (ref "LED111") (pin "3") (pinfunction "VCC_3") (pintype "passive"))
      (node (ref "LED112") (pin "3") (pinfunction "VCC_3") (pintype "passive"))
      (node (ref "LED12") (pin "3") (pinfunction "VCC_3") (pintype "passive"))
      (node (ref "LED13") (pin "3") (pinfunction "VCC_3") (pintype "passive"))
      (node (ref "LED14") (pin "3") (pinfunction "VCC_3") (pintype "passive"))
      (node (ref "LED15") (pin "3") (pinfunction "VCC_3") (pintype "passive"))
      (node (ref "LED16") (pin "3") (pinfunction "VCC_3") (pintype "passive"))
      (node (ref "LED17") (pin "3") (pinfunction "VCC_3") (pintype "passive"))
      (node (ref "LED19") (pin "3") (pinfunction "VCC_3") (pintype "passive"))
      (node (ref "LED20") (pin "3") (pinfunction "VCC_3") (pintype "passive"))
      (node (ref "LED21") (pin "3") (pinfunction "VCC_3") (pintype "passive"))
      (node (ref "LED22") (pin "3") (pinfunction "VCC_3") (pintype "passive"))
      (node (ref "LED23") (pin "3") (pinfunction "VCC_3") (pintype "passive"))
      (node (ref "LED24") (pin "3") (pinfunction "VCC_3") (pintype "passive"))
      (node (ref "LED25") (pin "3") (pinfunction "VCC_3") (pintype "passive"))
      (node (ref "LED26") (pin "3") (pinfunction "VCC_3") (pintype "passive"))
      (node (ref "LED27") (pin "3") (pinfunction "VCC_3") (pintype "passive"))
      (node (ref "LED28") (pin "3") (pinfunction "VCC_3") (pintype "passive"))
      (node (ref "LED29") (pin "3") (pinfunction "VCC_3") (pintype "passive"))
      (node (ref "LED30") (pin "3") (pinfunction "VCC_3") (pintype "passive"))
      (node (ref "LED31") (pin "3") (pinfunction "VCC_3") (pintype "passive"))
      (node (ref "LED32") (pin "3") (pinfunction "VCC_3") (pintype "passive"))
      (node (ref "LED33") (pin "3") (pinfunction "VCC_3") (pintype "passive"))
      (node (ref "LED34") (pin "3") (pinfunction "VCC_3") (pintype "passive"))
      (node (ref "LED35") (pin "3") (pinfunction "VCC_3") (pintype "passive"))
      (node (ref "LED36") (pin "3") (pinfunction "VCC_3") (pintype "passive"))
      (node (ref "LED38") (pin "3") (pinfunction "VCC_3") (pintype "passive"))
      (node (ref "LED39") (pin "3") (pinfunction "VCC_3") (pintype "passive"))
      (node (ref "LED40") (pin "3") (pinfunction "VCC_3") (pintype "passive"))
      (node (ref "LED41") (pin "3") (pinfunction "VCC_3") (pintype "passive"))
      (node (ref "LED42") (pin "3") (pinfunction "VCC_3") (pintype "passive"))
      (node (ref "LED43") (pin "3") (pinfunction "VCC_3") (pintype "passive"))
      (node (ref "LED44") (pin "3") (pinfunction "VCC_3") (pintype "passive"))
      (node (ref "LED45") (pin "3") (pinfunction "VCC_3") (pintype "passive"))
      (node (ref "LED46") (pin "3") (pinfunction "VCC_3") (pintype "passive"))
      (node (ref "LED47") (pin "3") (pinfunction "VCC_3") (pintype "passive"))
      (node (ref "LED48") (pin "3") (pinfunction "VCC_3") (pintype "passive"))
      (node (ref "LED49") (pin "3") (pinfunction "VCC_3") (pintype "passive"))
      (node (ref "LED50") (pin "3") (pinfunction "VCC_3") (pintype "passive"))
      (node (ref "LED51") (pin "3") (pinfunction "VCC_3") (pintype "passive"))
      (node (ref "LED52") (pin "3") (pinfunction "VCC_3") (pintype "passive"))
      (node (ref "LED53") (pin "3") (pinfunction "VCC_3") (pintype "passive"))
      (node (ref "LED54") (pin "3") (pinfunction "VCC_3") (pintype "passive"))
      (node (ref "LED55") (pin "3") (pinfunction "VCC_3") (pintype "passive"))
      (node (ref "LED6") (pin "3") (pinfunction "VCC_3") (pintype "passive"))
      (node (ref "LED63") (pin "3") (pinfunction "VCC_3") (pintype "passive"))
      (node (ref "LED64") (pin "3") (pinfunction "VCC_3") (pintype "passive"))
      (node (ref "LED65") (pin "3") (pinfunction "VCC_3") (pintype "passive"))
      (node (ref "LED66") (pin "3") (pinfunction "VCC_3") (pintype "passive"))
      (node (ref "LED67") (pin "3") (pinfunction "VCC_3") (pintype "passive"))
      (node (ref "LED68") (pin "3") (pinfunction "VCC_3") (pintype "passive"))
      (node (ref "LED69") (pin "3") (pinfunction "VCC_3") (pintype "passive"))
      (node (ref "LED7") (pin "3") (pinfunction "VCC_3") (pintype "passive"))
      (node (ref "LED70") (pin "3") (pinfunction "VCC_3") (pintype "passive"))
      (node (ref "LED71") (pin "3") (pinfunction "VCC_3") (pintype "passive"))
      (node (ref "LED72") (pin "3") (pinfunction "VCC_3") (pintype "passive"))
      (node (ref "LED73") (pin "3") (pinfunction "VCC_3") (pintype "passive"))
      (node (ref "LED74") (pin "3") (pinfunction "VCC_3") (pintype "passive"))
      (node (ref "LED75") (pin "3") (pinfunction "VCC_3") (pintype "passive"))
      (node (ref "LED76") (pin "3") (pinfunction "VCC_3") (pintype "passive"))
      (node (ref "LED77") (pin "3") (pinfunction "VCC_3") (pintype "passive"))
      (node (ref "LED78") (pin "3") (pinfunction "VCC_3") (pintype "passive"))
      (node (ref "LED79") (pin "3") (pinfunction "VCC_3") (pintype "passive"))
      (node (ref "LED8") (pin "3") (pinfunction "VCC_3") (pintype "passive"))
      (node (ref "LED80") (pin "3") (pinfunction "VCC_3") (pintype "passive"))
      (node (ref "LED82") (pin "3") (pinfunction "VCC_3") (pintype "passive"))
      (node (ref "LED83") (pin "3") (pinfunction "VCC_3") (pintype "passive"))
      (node (ref "LED84") (pin "3") (pinfunction "VCC_3") (pintype "passive"))
      (node (ref "LED85") (pin "3") (pinfunction "VCC_3") (pintype "passive"))
      (node (ref "LED86") (pin "3") (pinfunction "VCC_3") (pintype "passive"))
      (node (ref "LED87") (pin "3") (pinfunction "VCC_3") (pintype "passive"))
      (node (ref "LED88") (pin "3") (pinfunction "VCC_3") (pintype "passive"))
      (node (ref "LED89") (pin "3") (pinfunction "VCC_3") (pintype "passive"))
      (node (ref "LED9") (pin "3") (pinfunction "VCC_3") (pintype "passive"))
      (node (ref "LED90") (pin "3") (pinfunction "VCC_3") (pintype "passive"))
      (node (ref "LED91") (pin "3") (pinfunction "VCC_3") (pintype "passive"))
      (node (ref "LED92") (pin "3") (pinfunction "VCC_3") (pintype "passive"))
      (node (ref "LED93") (pin "3") (pinfunction "VCC_3") (pintype "passive"))
      (node (ref "LED94") (pin "3") (pinfunction "VCC_3") (pintype "passive"))
      (node (ref "LED95") (pin "3") (pinfunction "VCC_3") (pintype "passive"))
      (node (ref "LED96") (pin "3") (pinfunction "VCC_3") (pintype "passive"))
      (node (ref "LED97") (pin "3") (pinfunction "VCC_3") (pintype "passive"))
      (node (ref "LED98") (pin "3") (pinfunction "VCC_3") (pintype "passive"))
      (node (ref "LED99") (pin "3") (pinfunction "VCC_3") (pintype "passive"))
      (node (ref "R14") (pin "2") (pinfunction "2_2") (pintype "passive"))
      (node (ref "U14") (pin "20") (pinfunction "VDD_20") (pintype "power_in"))
      (node (ref "U15") (pin "20") (pinfunction "VDD_20") (pintype "power_in"))
      (node (ref "U16") (pin "20") (pinfunction "VDD_20") (pintype "power_in"))
      (node (ref "U17") (pin "20") (pinfunction "VDD_20") (pintype "power_in"))
      (node (ref "U18") (pin "20") (pinfunction "VDD_20") (pintype "power_in"))
      (node (ref "U19") (pin "20") (pinfunction "VDD_20") (pintype "power_in"))
      (node (ref "U2") (pin "20") (pinfunction "VDD_20") (pintype "power_in"))
      (node (ref "U3") (pin "20") (pinfunction "VDD_20") (pintype "power_in"))
      (node (ref "U4") (pin "20") (pinfunction "VDD_20") (pintype "power_in"))
      (node (ref "U5") (pin "20") (pinfunction "VDD_20") (pintype "power_in"))
      (node (ref "U6") (pin "20") (pinfunction "VDD_20") (pintype "power_in"))
      (node (ref "U7") (pin "20") (pinfunction "VDD_20") (pintype "power_in"))
    )
    (net (code "96") (name "GND") (class "Default")
      (node (ref "C10") (pin "1") (pinfunction "1_1") (pintype "passive"))
      (node (ref "C11") (pin "1") (pinfunction "1_1") (pintype "passive"))
      (node (ref "C12") (pin "1") (pinfunction "1_1") (pintype "passive"))
      (node (ref "C13") (pin "1") (pinfunction "1_1") (pintype "passive"))
      (node (ref "C2") (pin "1") (pinfunction "1_1") (pintype "passive"))
      (node (ref "C3") (pin "1") (pinfunction "1_1") (pintype "passive"))
      (node (ref "C4") (pin "1") (pinfunction "1_1") (pintype "passive"))
      (node (ref "C5") (pin "1") (pinfunction "1_1") (pintype "passive"))
      (node (ref "C6") (pin "1") (pinfunction "1_1") (pintype "passive"))
      (node (ref "C7") (pin "1") (pinfunction "1_1") (pintype "passive"))
      (node (ref "C8") (pin "1") (pinfunction "1_1") (pintype "passive"))
      (node (ref "C9") (pin "1") (pinfunction "1_1") (pintype "passive"))
      (node (ref "LED1") (pin "2") (pinfunction "K_2") (pintype "passive"))
      (node (ref "LED10") (pin "1") (pinfunction "GND_1") (pintype "passive"))
      (node (ref "LED100") (pin "2") (pinfunction "K_2") (pintype "passive"))
      (node (ref "LED101") (pin "1") (pinfunction "GND_1") (pintype "passive"))
      (node (ref "LED102") (pin "1") (pinfunction "GND_1") (pintype "passive"))
      (node (ref "LED103") (pin "1") (pinfunction "GND_1") (pintype "passive"))
      (node (ref "LED104") (pin "1") (pinfunction "GND_1") (pintype "passive"))
      (node (ref "LED105") (pin "1") (pinfunction "GND_1") (pintype "passive"))
      (node (ref "LED106") (pin "1") (pinfunction "GND_1") (pintype "passive"))
      (node (ref "LED107") (pin "1") (pinfunction "GND_1") (pintype "passive"))
      (node (ref "LED108") (pin "1") (pinfunction "GND_1") (pintype "passive"))
      (node (ref "LED109") (pin "1") (pinfunction "GND_1") (pintype "passive"))
      (node (ref "LED11") (pin "1") (pinfunction "GND_1") (pintype "passive"))
      (node (ref "LED111") (pin "1") (pinfunction "GND_1") (pintype "passive"))
      (node (ref "LED112") (pin "1") (pinfunction "GND_1") (pintype "passive"))
      (node (ref "LED12") (pin "1") (pinfunction "GND_1") (pintype "passive"))
      (node (ref "LED13") (pin "1") (pinfunction "GND_1") (pintype "passive"))
      (node (ref "LED14") (pin "1") (pinfunction "GND_1") (pintype "passive"))
      (node (ref "LED15") (pin "1") (pinfunction "GND_1") (pintype "passive"))
      (node (ref "LED16") (pin "1") (pinfunction "GND_1") (pintype "passive"))
      (node (ref "LED17") (pin "1") (pinfunction "GND_1") (pintype "passive"))
      (node (ref "LED18") (pin "2") (pinfunction "K_2") (pintype "passive"))
      (node (ref "LED19") (pin "1") (pinfunction "GND_1") (pintype "passive"))
      (node (ref "LED2") (pin "2") (pinfunction "K_2") (pintype "passive"))
      (node (ref "LED20") (pin "1") (pinfunction "GND_1") (pintype "passive"))
      (node (ref "LED21") (pin "1") (pinfunction "GND_1") (pintype "passive"))
      (node (ref "LED22") (pin "1") (pinfunction "GND_1") (pintype "passive"))
      (node (ref "LED23") (pin "1") (pinfunction "GND_1") (pintype "passive"))
      (node (ref "LED24") (pin "1") (pinfunction "GND_1") (pintype "passive"))
      (node (ref "LED25") (pin "1") (pinfunction "GND_1") (pintype "passive"))
      (node (ref "LED26") (pin "1") (pinfunction "GND_1") (pintype "passive"))
      (node (ref "LED27") (pin "1") (pinfunction "GND_1") (pintype "passive"))
      (node (ref "LED28") (pin "1") (pinfunction "GND_1") (pintype "passive"))
      (node (ref "LED29") (pin "1") (pinfunction "GND_1") (pintype "passive"))
      (node (ref "LED3") (pin "2") (pinfunction "K_2") (pintype "passive"))
      (node (ref "LED30") (pin "1") (pinfunction "GND_1") (pintype "passive"))
      (node (ref "LED31") (pin "1") (pinfunction "GND_1") (pintype "passive"))
      (node (ref "LED32") (pin "1") (pinfunction "GND_1") (pintype "passive"))
      (node (ref "LED33") (pin "1") (pinfunction "GND_1") (pintype "passive"))
      (node (ref "LED34") (pin "1") (pinfunction "GND_1") (pintype "passive"))
      (node (ref "LED35") (pin "1") (pinfunction "GND_1") (pintype "passive"))
      (node (ref "LED36") (pin "1") (pinfunction "GND_1") (pintype "passive"))
      (node (ref "LED37") (pin "2") (pinfunction "K_2") (pintype "passive"))
      (node (ref "LED38") (pin "1") (pinfunction "GND_1") (pintype "passive"))
      (node (ref "LED39") (pin "1") (pinfunction "GND_1") (pintype "passive"))
      (node (ref "LED4") (pin "2") (pinfunction "K_2") (pintype "passive"))
      (node (ref "LED40") (pin "1") (pinfunction "GND_1") (pintype "passive"))
      (node (ref "LED41") (pin "1") (pinfunction "GND_1") (pintype "passive"))
      (node (ref "LED42") (pin "1") (pinfunction "GND_1") (pintype "passive"))
      (node (ref "LED43") (pin "1") (pinfunction "GND_1") (pintype "passive"))
      (node (ref "LED44") (pin "1") (pinfunction "GND_1") (pintype "passive"))
      (node (ref "LED45") (pin "1") (pinfunction "GND_1") (pintype "passive"))
      (node (ref "LED46") (pin "1") (pinfunction "GND_1") (pintype "passive"))
      (node (ref "LED47") (pin "1") (pinfunction "GND_1") (pintype "passive"))
      (node (ref "LED48") (pin "1") (pinfunction "GND_1") (pintype "passive"))
      (node (ref "LED49") (pin "1") (pinfunction "GND_1") (pintype "passive"))
      (node (ref "LED5") (pin "2") (pinfunction "K_2") (pintype "passive"))
      (node (ref "LED50") (pin "1") (pinfunction "GND_1") (pintype "passive"))
      (node (ref "LED51") (pin "1") (pinfunction "GND_1") (pintype "passive"))
      (node (ref "LED52") (pin "1") (pinfunction "GND_1") (pintype "passive"))
      (node (ref "LED53") (pin "1") (pinfunction "GND_1") (pintype "passive"))
      (node (ref "LED54") (pin "1") (pinfunction "GND_1") (pintype "passive"))
      (node (ref "LED55") (pin "1") (pinfunction "GND_1") (pintype "passive"))
      (node (ref "LED56") (pin "2") (pinfunction "K_2") (pintype "passive"))
      (node (ref "LED57") (pin "2") (pinfunction "K_2") (pintype "passive"))
      (node (ref "LED58") (pin "2") (pinfunction "K_2") (pintype "passive"))
      (node (ref "LED59") (pin "2") (pinfunction "K_2") (pintype "passive"))
      (node (ref "LED6") (pin "1") (pinfunction "GND_1") (pintype "passive"))
      (node (ref "LED60") (pin "2") (pinfunction "K_2") (pintype "passive"))
      (node (ref "LED61") (pin "2") (pinfunction "K_2") (pintype "passive"))
      (node (ref "LED62") (pin "2") (pinfunction "K_2") (pintype "passive"))
      (node (ref "LED63") (pin "1") (pinfunction "GND_1") (pintype "passive"))
      (node (ref "LED64") (pin "1") (pinfunction "GND_1") (pintype "passive"))
      (node (ref "LED65") (pin "1") (pinfunction "GND_1") (pintype "passive"))
      (node (ref "LED66") (pin "1") (pinfunction "GND_1") (pintype "passive"))
      (node (ref "LED67") (pin "1") (pinfunction "GND_1") (pintype "passive"))
      (node (ref "LED68") (pin "1") (pinfunction "GND_1") (pintype "passive"))
      (node (ref "LED69") (pin "1") (pinfunction "GND_1") (pintype "passive"))
      (node (ref "LED7") (pin "1") (pinfunction "GND_1") (pintype "passive"))
      (node (ref "LED70") (pin "1") (pinfunction "GND_1") (pintype "passive"))
      (node (ref "LED71") (pin "1") (pinfunction "GND_1") (pintype "passive"))
      (node (ref "LED72") (pin "1") (pinfunction "GND_1") (pintype "passive"))
      (node (ref "LED73") (pin "1") (pinfunction "GND_1") (pintype "passive"))
      (node (ref "LED74") (pin "1") (pinfunction "GND_1") (pintype "passive"))
      (node (ref "LED75") (pin "1") (pinfunction "GND_1") (pintype "passive"))
      (node (ref "LED76") (pin "1") (pinfunction "GND_1") (pintype "passive"))
      (node (ref "LED77") (pin "1") (pinfunction "GND_1") (pintype "passive"))
      (node (ref "LED78") (pin "1") (pinfunction "GND_1") (pintype "passive"))
      (node (ref "LED79") (pin "1") (pinfunction "GND_1") (pintype "passive"))
      (node (ref "LED8") (pin "1") (pinfunction "GND_1") (pintype "passive"))
      (node (ref "LED80") (pin "1") (pinfunction "GND_1") (pintype "passive"))
      (node (ref "LED81") (pin "2") (pinfunction "K_2") (pintype "passive"))
      (node (ref "LED82") (pin "1") (pinfunction "GND_1") (pintype "passive"))
      (node (ref "LED83") (pin "1") (pinfunction "GND_1") (pintype "passive"))
      (node (ref "LED84") (pin "1") (pinfunction "GND_1") (pintype "passive"))
      (node (ref "LED85") (pin "1") (pinfunction "GND_1") (pintype "passive"))
      (node (ref "LED86") (pin "1") (pinfunction "GND_1") (pintype "passive"))
      (node (ref "LED87") (pin "1") (pinfunction "GND_1") (pintype "passive"))
      (node (ref "LED88") (pin "1") (pinfunction "GND_1") (pintype "passive"))
      (node (ref "LED89") (pin "1") (pinfunction "GND_1") (pintype "passive"))
      (node (ref "LED9") (pin "1") (pinfunction "GND_1") (pintype "passive"))
      (node (ref "LED90") (pin "1") (pinfunction "GND_1") (pintype "passive"))
      (node (ref "LED91") (pin "1") (pinfunction "GND_1") (pintype "passive"))
      (node (ref "LED92") (pin "1") (pinfunction "GND_1") (pintype "passive"))
      (node (ref "LED93") (pin "1") (pinfunction "GND_1") (pintype "passive"))
      (node (ref "LED94") (pin "1") (pinfunction "GND_1") (pintype "passive"))
      (node (ref "LED95") (pin "1") (pinfunction "GND_1") (pintype "passive"))
      (node (ref "LED96") (pin "1") (pinfunction "GND_1") (pintype "passive"))
      (node (ref "LED97") (pin "1") (pinfunction "GND_1") (pintype "passive"))
      (node (ref "LED98") (pin "1") (pinfunction "GND_1") (pintype "passive"))
      (node (ref "LED99") (pin "1") (pinfunction "GND_1") (pintype "passive"))
      (node (ref "U14") (pin "1") (pinfunction "~{OE}1_1") (pintype "input"))
      (node (ref "U14") (pin "10") (pinfunction "GND_10") (pintype "power_in"))
      (node (ref "U14") (pin "19") (pinfunction "~{OE}2_19") (pintype "input"))
      (node (ref "U15") (pin "1") (pinfunction "~{OE}1_1") (pintype "input"))
      (node (ref "U15") (pin "10") (pinfunction "GND_10") (pintype "power_in"))
      (node (ref "U15") (pin "19") (pinfunction "~{OE}2_19") (pintype "input"))
      (node (ref "U16") (pin "1") (pinfunction "~{OE}1_1") (pintype "input"))
      (node (ref "U16") (pin "10") (pinfunction "GND_10") (pintype "power_in"))
      (node (ref "U16") (pin "19") (pinfunction "~{OE}2_19") (pintype "input"))
      (node (ref "U17") (pin "1") (pinfunction "~{OE}1_1") (pintype "input"))
      (node (ref "U17") (pin "10") (pinfunction "GND_10") (pintype "power_in"))
      (node (ref "U17") (pin "19") (pinfunction "~{OE}2_19") (pintype "input"))
      (node (ref "U18") (pin "1") (pinfunction "~{OE}1_1") (pintype "input"))
      (node (ref "U18") (pin "10") (pinfunction "GND_10") (pintype "power_in"))
      (node (ref "U18") (pin "19") (pinfunction "~{OE}2_19") (pintype "input"))
      (node (ref "U19") (pin "1") (pinfunction "~{OE}1_1") (pintype "input"))
      (node (ref "U19") (pin "19") (pinfunction "~{OE}2_19") (pintype "input"))
      (node (ref "U2") (pin "1") (pinfunction "~{OE}1_1") (pintype "input"))
      (node (ref "U2") (pin "10") (pinfunction "GND_10") (pintype "power_in"))
      (node (ref "U2") (pin "19") (pinfunction "~{OE}2_19") (pintype "input"))
      (node (ref "U3") (pin "1") (pinfunction "~{OE}1_1") (pintype "input"))
      (node (ref "U3") (pin "10") (pinfunction "GND_10") (pintype "power_in"))
      (node (ref "U3") (pin "19") (pinfunction "~{OE}2_19") (pintype "input"))
      (node (ref "U4") (pin "1") (pinfunction "~{OE}1_1") (pintype "input"))
      (node (ref "U4") (pin "10") (pinfunction "GND_10") (pintype "power_in"))
      (node (ref "U4") (pin "19") (pinfunction "~{OE}2_19") (pintype "input"))
      (node (ref "U5") (pin "1") (pinfunction "~{OE}1_1") (pintype "input"))
      (node (ref "U5") (pin "10") (pinfunction "GND_10") (pintype "power_in"))
      (node (ref "U5") (pin "19") (pinfunction "~{OE}2_19") (pintype "input"))
      (node (ref "U6") (pin "1") (pinfunction "~{OE}1_1") (pintype "input"))
      (node (ref "U6") (pin "10") (pinfunction "GND_10") (pintype "power_in"))
      (node (ref "U6") (pin "19") (pinfunction "~{OE}2_19") (pintype "input"))
      (node (ref "U7") (pin "1") (pinfunction "~{OE}1_1") (pintype "input"))
      (node (ref "U7") (pin "10") (pinfunction "GND_10") (pintype "power_in"))
      (node (ref "U7") (pin "19") (pinfunction "~{OE}2_19") (pintype "input"))
    )
    (net (code "97") (name "Net-(LED1-A)") (class "Default")
      (node (ref "LED1") (pin "1") (pinfunction "A_1") (pintype "passive"))
      (node (ref "R12") (pin "1") (pinfunction "1_1") (pintype "passive"))
    )
    (net (code "98") (name "Net-(LED2-A)") (class "Default")
      (node (ref "LED2") (pin "1") (pinfunction "A_1") (pintype "passive"))
      (node (ref "R13") (pin "1") (pinfunction "1_1") (pintype "passive"))
    )
    (net (code "99") (name "Net-(LED3-A)") (class "Default")
      (node (ref "LED3") (pin "1") (pinfunction "A_1") (pintype "passive"))
      (node (ref "R14") (pin "1") (pinfunction "1_1") (pintype "passive"))
    )
    (net (code "100") (name "Net-(LED4-A)") (class "Default")
      (node (ref "LED4") (pin "1") (pinfunction "A_1") (pintype "passive"))
      (node (ref "R15") (pin "1") (pinfunction "1_1") (pintype "passive"))
    )
    (net (code "101") (name "Net-(LED5-A)") (class "Default")
      (node (ref "LED5") (pin "1") (pinfunction "A_1") (pintype "passive"))
      (node (ref "R16") (pin "1") (pinfunction "1_1") (pintype "passive"))
    )
    (net (code "102") (name "Net-(LED6-RES)") (class "Default")
      (node (ref "LED6") (pin "2") (pinfunction "RES_2") (pintype "passive"))
      (node (ref "U8") (pin "16") (pinfunction "1B_16") (pintype "passive"))
    )
    (net (code "103") (name "Net-(LED7-RES)") (class "Default")
      (node (ref "LED7") (pin "2") (pinfunction "RES_2") (pintype "passive"))
      (node (ref "U9") (pin "16") (pinfunction "1B_16") (pintype "passive"))
    )
    (net (code "104") (name "Net-(LED8-RES)") (class "Default")
      (node (ref "LED8") (pin "2") (pinfunction "RES_2") (pintype "passive"))
      (node (ref "U10") (pin "16") (pinfunction "1B_16") (pintype "passive"))
    )
    (net (code "105") (name "Net-(LED9-RES)") (class "Default")
      (node (ref "LED9") (pin "2") (pinfunction "RES_2") (pintype "passive"))
      (node (ref "U21") (pin "12") (pinfunction "5B_12") (pintype "passive"))
    )
    (net (code "106") (name "Net-(LED10-RES)") (class "Default")
      (node (ref "LED10") (pin "2") (pinfunction "RES_2") (pintype "passive"))
      (node (ref "U12") (pin "16") (pinfunction "1B_16") (pintype "passive"))
    )
    (net (code "107") (name "Net-(LED11-RES)") (class "Default")
      (node (ref "LED11") (pin "2") (pinfunction "RES_2") (pintype "passive"))
      (node (ref "U13") (pin "16") (pinfunction "1B_16") (pintype "passive"))
    )
    (net (code "108") (name "Net-(LED12-RES)") (class "Default")
      (node (ref "LED12") (pin "2") (pinfunction "RES_2") (pintype "passive"))
      (node (ref "U8") (pin "15") (pinfunction "2B_15") (pintype "passive"))
    )
    (net (code "109") (name "Net-(LED13-RES)") (class "Default")
      (node (ref "LED13") (pin "2") (pinfunction "RES_2") (pintype "passive"))
      (node (ref "U9") (pin "15") (pinfunction "2B_15") (pintype "passive"))
    )
    (net (code "110") (name "Net-(LED14-RES)") (class "Default")
      (node (ref "LED14") (pin "2") (pinfunction "RES_2") (pintype "passive"))
      (node (ref "U10") (pin "15") (pinfunction "2B_15") (pintype "passive"))
    )
    (net (code "111") (name "Net-(LED15-RES)") (class "Default")
      (node (ref "LED15") (pin "2") (pinfunction "RES_2") (pintype "passive"))
      (node (ref "U21") (pin "11") (pinfunction "6B_11") (pintype "passive"))
    )
    (net (code "112") (name "Net-(LED16-RES)") (class "Default")
      (node (ref "LED16") (pin "2") (pinfunction "RES_2") (pintype "passive"))
      (node (ref "U12") (pin "15") (pinfunction "2B_15") (pintype "passive"))
    )
    (net (code "113") (name "Net-(LED17-RES)") (class "Default")
      (node (ref "LED17") (pin "2") (pinfunction "RES_2") (pintype "passive"))
      (node (ref "U13") (pin "15") (pinfunction "2B_15") (pintype "passive"))
    )
    (net (code "114") (name "Net-(LED18-A)") (class "Default")
      (node (ref "LED18") (pin "1") (pinfunction "A_1") (pintype "passive"))
      (node (ref "R17") (pin "1") (pinfunction "1_1") (pintype "passive"))
    )
    (net (code "115") (name "Net-(LED19-RES)") (class "Default")
      (node (ref "LED19") (pin "2") (pinfunction "RES_2") (pintype "passive"))
      (node (ref "U8") (pin "14") (pinfunction "3B_14") (pintype "passive"))
    )
    (net (code "116") (name "Net-(LED20-RES)") (class "Default")
      (node (ref "LED20") (pin "2") (pinfunction "RES_2") (pintype "passive"))
      (node (ref "U9") (pin "14") (pinfunction "3B_14") (pintype "passive"))
    )
    (net (code "117") (name "Net-(LED21-RES)") (class "Default")
      (node (ref "LED21") (pin "2") (pinfunction "RES_2") (pintype "passive"))
      (node (ref "U10") (pin "14") (pinfunction "3B_14") (pintype "passive"))
    )
    (net (code "118") (name "Net-(LED22-RES)") (class "Default")
      (node (ref "LED22") (pin "2") (pinfunction "RES_2") (pintype "passive"))
      (node (ref "U11") (pin "14") (pinfunction "3B_14") (pintype "passive"))
    )
    (net (code "119") (name "Net-(LED23-RES)") (class "Default")
      (node (ref "LED23") (pin "2") (pinfunction "RES_2") (pintype "passive"))
      (node (ref "U12") (pin "14") (pinfunction "3B_14") (pintype "passive"))
    )
    (net (code "120") (name "Net-(LED24-RES)") (class "Default")
      (node (ref "LED24") (pin "2") (pinfunction "RES_2") (pintype "passive"))
      (node (ref "U13") (pin "14") (pinfunction "3B_14") (pintype "passive"))
    )
    (net (code "121") (name "Net-(LED25-RES)") (class "Default")
      (node (ref "LED25") (pin "2") (pinfunction "RES_2") (pintype "passive"))
      (node (ref "U8") (pin "13") (pinfunction "4B_13") (pintype "passive"))
    )
    (net (code "122") (name "Net-(LED26-RES)") (class "Default")
      (node (ref "LED26") (pin "2") (pinfunction "RES_2") (pintype "passive"))
      (node (ref "U9") (pin "13") (pinfunction "4B_13") (pintype "passive"))
    )
    (net (code "123") (name "Net-(LED27-RES)") (class "Default")
      (node (ref "LED27") (pin "2") (pinfunction "RES_2") (pintype "passive"))
      (node (ref "U10") (pin "13") (pinfunction "4B_13") (pintype "passive"))
    )
    (net (code "124") (name "Net-(LED28-RES)") (class "Default")
      (node (ref "LED28") (pin "2") (pinfunction "RES_2") (pintype "passive"))
      (node (ref "U11") (pin "13") (pinfunction "4B_13") (pintype "passive"))
    )
    (net (code "125") (name "Net-(LED29-RES)") (class "Default")
      (node (ref "LED29") (pin "2") (pinfunction "RES_2") (pintype "passive"))
      (node (ref "U12") (pin "13") (pinfunction "4B_13") (pintype "passive"))
    )
    (net (code "126") (name "Net-(LED30-RES)") (class "Default")
      (node (ref "LED30") (pin "2") (pinfunction "RES_2") (pintype "passive"))
      (node (ref "U13") (pin "13") (pinfunction "4B_13") (pintype "passive"))
    )
    (net (code "127") (name "Net-(LED31-RES)") (class "Default")
      (node (ref "LED31") (pin "2") (pinfunction "RES_2") (pintype "passive"))
      (node (ref "U8") (pin "12") (pinfunction "5B_12") (pintype "passive"))
    )
    (net (code "128") (name "Net-(LED32-RES)") (class "Default")
      (node (ref "LED32") (pin "2") (pinfunction "RES_2") (pintype "passive"))
      (node (ref "U9") (pin "12") (pinfunction "5B_12") (pintype "passive"))
    )
    (net (code "129") (name "Net-(LED33-RES)") (class "Default")
      (node (ref "LED33") (pin "2") (pinfunction "RES_2") (pintype "passive"))
      (node (ref "U10") (pin "12") (pinfunction "5B_12") (pintype "passive"))
    )
    (net (code "130") (name "Net-(LED34-RES)") (class "Default")
      (node (ref "LED34") (pin "2") (pinfunction "RES_2") (pintype "passive"))
      (node (ref "U11") (pin "12") (pinfunction "5B_12") (pintype "passive"))
    )
    (net (code "131") (name "Net-(LED35-RES)") (class "Default")
      (node (ref "LED35") (pin "2") (pinfunction "RES_2") (pintype "passive"))
      (node (ref "U12") (pin "12") (pinfunction "5B_12") (pintype "passive"))
    )
    (net (code "132") (name "Net-(LED36-RES)") (class "Default")
      (node (ref "LED36") (pin "2") (pinfunction "RES_2") (pintype "passive"))
      (node (ref "U13") (pin "12") (pinfunction "5B_12") (pintype "passive"))
    )
    (net (code "133") (name "Net-(LED37-A)") (class "Default")
      (node (ref "LED37") (pin "1") (pinfunction "A_1") (pintype "passive"))
      (node (ref "R18") (pin "1") (pinfunction "1_1") (pintype "passive"))
    )
    (net (code "134") (name "Net-(LED38-RES)") (class "Default")
      (node (ref "LED38") (pin "2") (pinfunction "RES_2") (pintype "passive"))
      (node (ref "U8") (pin "11") (pinfunction "6B_11") (pintype "passive"))
    )
    (net (code "135") (name "Net-(LED39-RES)") (class "Default")
      (node (ref "LED39") (pin "2") (pinfunction "RES_2") (pintype "passive"))
      (node (ref "U9") (pin "11") (pinfunction "6B_11") (pintype "passive"))
    )
    (net (code "136") (name "Net-(LED40-RES)") (class "Default")
      (node (ref "LED40") (pin "2") (pinfunction "RES_2") (pintype "passive"))
      (node (ref "U10") (pin "11") (pinfunction "6B_11") (pintype "passive"))
    )
    (net (code "137") (name "Net-(LED41-RES)") (class "Default")
      (node (ref "LED41") (pin "2") (pinfunction "RES_2") (pintype "passive"))
      (node (ref "U11") (pin "11") (pinfunction "6B_11") (pintype "passive"))
    )
    (net (code "138") (name "Net-(LED42-RES)") (class "Default")
      (node (ref "LED42") (pin "2") (pinfunction "RES_2") (pintype "passive"))
      (node (ref "U12") (pin "11") (pinfunction "6B_11") (pintype "passive"))
    )
    (net (code "139") (name "Net-(LED43-RES)") (class "Default")
      (node (ref "LED43") (pin "2") (pinfunction "RES_2") (pintype "passive"))
      (node (ref "U13") (pin "11") (pinfunction "6B_11") (pintype "passive"))
    )
    (net (code "140") (name "Net-(LED44-RES)") (class "Default")
      (node (ref "LED44") (pin "2") (pinfunction "RES_2") (pintype "passive"))
      (node (ref "U8") (pin "10") (pinfunction "7B_10") (pintype "passive"))
    )
    (net (code "141") (name "Net-(LED45-RES)") (class "Default")
      (node (ref "LED45") (pin "2") (pinfunction "RES_2") (pintype "passive"))
      (node (ref "U9") (pin "10") (pinfunction "7B_10") (pintype "passive"))
    )
    (net (code "142") (name "Net-(LED46-RES)") (class "Default")
      (node (ref "LED46") (pin "2") (pinfunction "RES_2") (pintype "passive"))
      (node (ref "U10") (pin "10") (pinfunction "7B_10") (pintype "passive"))
    )
    (net (code "143") (name "Net-(LED47-RES)") (class "Default")
      (node (ref "LED47") (pin "2") (pinfunction "RES_2") (pintype "passive"))
      (node (ref "U11") (pin "10") (pinfunction "7B_10") (pintype "passive"))
    )
    (net (code "144") (name "Net-(LED48-RES)") (class "Default")
      (node (ref "LED48") (pin "2") (pinfunction "RES_2") (pintype "passive"))
      (node (ref "U12") (pin "10") (pinfunction "7B_10") (pintype "passive"))
    )
    (net (code "145") (name "Net-(LED49-RES)") (class "Default")
      (node (ref "LED49") (pin "2") (pinfunction "RES_2") (pintype "passive"))
      (node (ref "U13") (pin "10") (pinfunction "7B_10") (pintype "passive"))
    )
    (net (code "146") (name "Net-(LED50-RES)") (class "Default")
      (node (ref "LED50") (pin "2") (pinfunction "RES_2") (pintype "passive"))
      (node (ref "U8") (pin "9") (pinfunction "8B_9") (pintype "passive"))
    )
    (net (code "147") (name "Net-(LED51-RES)") (class "Default")
      (node (ref "LED51") (pin "2") (pinfunction "RES_2") (pintype "passive"))
      (node (ref "U9") (pin "9") (pinfunction "8B_9") (pintype "passive"))
    )
    (net (code "148") (name "Net-(LED52-RES)") (class "Default")
      (node (ref "LED52") (pin "2") (pinfunction "RES_2") (pintype "passive"))
      (node (ref "U10") (pin "9") (pinfunction "8B_9") (pintype "passive"))
    )
    (net (code "149") (name "Net-(LED53-RES)") (class "Default")
      (node (ref "LED53") (pin "2") (pinfunction "RES_2") (pintype "passive"))
      (node (ref "U11") (pin "9") (pinfunction "8B_9") (pintype "passive"))
    )
    (net (code "150") (name "Net-(LED54-RES)") (class "Default")
      (node (ref "LED54") (pin "2") (pinfunction "RES_2") (pintype "passive"))
      (node (ref "U12") (pin "9") (pinfunction "8B_9") (pintype "passive"))
    )
    (net (code "151") (name "Net-(LED55-RES)") (class "Default")
      (node (ref "LED55") (pin "2") (pinfunction "RES_2") (pintype "passive"))
      (node (ref "U13") (pin "9") (pinfunction "8B_9") (pintype "passive"))
    )
    (net (code "152") (name "Net-(LED56-A)") (class "Default")
      (node (ref "LED56") (pin "1") (pinfunction "A_1") (pintype "passive"))
      (node (ref "R19") (pin "1") (pinfunction "1_1") (pintype "passive"))
    )
    (net (code "153") (name "Net-(LED57-A)") (class "Default")
      (node (ref "LED57") (pin "1") (pinfunction "A_1") (pintype "passive"))
      (node (ref "R20") (pin "1") (pinfunction "1_1") (pintype "passive"))
    )
    (net (code "154") (name "Net-(LED58-A)") (class "Default")
      (node (ref "LED58") (pin "1") (pinfunction "A_1") (pintype "passive"))
      (node (ref "R21") (pin "1") (pinfunction "1_1") (pintype "passive"))
    )
    (net (code "155") (name "Net-(LED59-A)") (class "Default")
      (node (ref "LED59") (pin "1") (pinfunction "A_1") (pintype "passive"))
      (node (ref "R22") (pin "1") (pinfunction "1_1") (pintype "passive"))
    )
    (net (code "156") (name "Net-(LED60-A)") (class "Default")
      (node (ref "LED60") (pin "1") (pinfunction "A_1") (pintype "passive"))
      (node (ref "R23") (pin "1") (pinfunction "1_1") (pintype "passive"))
    )
    (net (code "157") (name "Net-(LED61-A)") (class "Default")
      (node (ref "LED61") (pin "1") (pinfunction "A_1") (pintype "passive"))
      (node (ref "R24") (pin "1") (pinfunction "1_1") (pintype "passive"))
    )
    (net (code "158") (name "Net-(LED62-A)") (class "Default")
      (node (ref "LED62") (pin "1") (pinfunction "A_1") (pintype "passive"))
      (node (ref "R25") (pin "1") (pinfunction "1_1") (pintype "passive"))
    )
    (net (code "159") (name "Net-(LED63-RES)") (class "Default")
      (node (ref "LED63") (pin "2") (pinfunction "RES_2") (pintype "passive"))
      (node (ref "U20") (pin "16") (pinfunction "1B_16") (pintype "passive"))
    )
    (net (code "160") (name "Net-(LED64-RES)") (class "Default")
      (node (ref "LED64") (pin "2") (pinfunction "RES_2") (pintype "passive"))
      (node (ref "U21") (pin "16") (pinfunction "1B_16") (pintype "passive"))
    )
    (net (code "161") (name "Net-(LED65-RES)") (class "Default")
      (node (ref "LED65") (pin "2") (pinfunction "RES_2") (pintype "passive"))
      (node (ref "U22") (pin "16") (pinfunction "1B_16") (pintype "passive"))
    )
    (net (code "162") (name "Net-(LED66-RES)") (class "Default")
      (node (ref "LED66") (pin "2") (pinfunction "RES_2") (pintype "passive"))
      (node (ref "U23") (pin "16") (pinfunction "1B_16") (pintype "passive"))
    )
    (net (code "163") (name "Net-(LED67-RES)") (class "Default")
      (node (ref "LED67") (pin "2") (pinfunction "RES_2") (pintype "passive"))
      (node (ref "U24") (pin "16") (pinfunction "1B_16") (pintype "passive"))
    )
    (net (code "164") (name "Net-(LED68-RES)") (class "Default")
      (node (ref "LED68") (pin "2") (pinfunction "RES_2") (pintype "passive"))
      (node (ref "U25") (pin "16") (pinfunction "1B_16") (pintype "passive"))
    )
    (net (code "165") (name "Net-(LED69-RES)") (class "Default")
      (node (ref "LED69") (pin "2") (pinfunction "RES_2") (pintype "passive"))
      (node (ref "U20") (pin "15") (pinfunction "2B_15") (pintype "passive"))
    )
    (net (code "166") (name "Net-(LED70-RES)") (class "Default")
      (node (ref "LED70") (pin "2") (pinfunction "RES_2") (pintype "passive"))
      (node (ref "U21") (pin "15") (pinfunction "2B_15") (pintype "passive"))
    )
    (net (code "167") (name "Net-(LED71-RES)") (class "Default")
      (node (ref "LED71") (pin "2") (pinfunction "RES_2") (pintype "passive"))
      (node (ref "U22") (pin "15") (pinfunction "2B_15") (pintype "passive"))
    )
    (net (code "168") (name "Net-(LED72-RES)") (class "Default")
      (node (ref "LED72") (pin "2") (pinfunction "RES_2") (pintype "passive"))
      (node (ref "U23") (pin "15") (pinfunction "2B_15") (pintype "passive"))
    )
    (net (code "169") (name "Net-(LED73-RES)") (class "Default")
      (node (ref "LED73") (pin "2") (pinfunction "RES_2") (pintype "passive"))
      (node (ref "U24") (pin "15") (pinfunction "2B_15") (pintype "passive"))
    )
    (net (code "170") (name "Net-(LED74-RES)") (class "Default")
      (node (ref "LED74") (pin "2") (pinfunction "RES_2") (pintype "passive"))
      (node (ref "U25") (pin "15") (pinfunction "2B_15") (pintype "passive"))
    )
    (net (code "171") (name "Net-(LED75-RES)") (class "Default")
      (node (ref "LED75") (pin "2") (pinfunction "RES_2") (pintype "passive"))
      (node (ref "U20") (pin "14") (pinfunction "3B_14") (pintype "passive"))
    )
    (net (code "172") (name "Net-(LED76-RES)") (class "Default")
      (node (ref "LED76") (pin "2") (pinfunction "RES_2") (pintype "passive"))
      (node (ref "U21") (pin "14") (pinfunction "3B_14") (pintype "passive"))
    )
    (net (code "173") (name "Net-(LED77-RES)") (class "Default")
      (node (ref "LED77") (pin "2") (pinfunction "RES_2") (pintype "passive"))
      (node (ref "U22") (pin "14") (pinfunction "3B_14") (pintype "passive"))
    )
    (net (code "174") (name "Net-(LED78-RES)") (class "Default")
      (node (ref "LED78") (pin "2") (pinfunction "RES_2") (pintype "passive"))
      (node (ref "U23") (pin "14") (pinfunction "3B_14") (pintype "passive"))
    )
    (net (code "175") (name "Net-(LED79-RES)") (class "Default")
      (node (ref "LED79") (pin "2") (pinfunction "RES_2") (pintype "passive"))
      (node (ref "U24") (pin "14") (pinfunction "3B_14") (pintype "passive"))
    )
    (net (code "176") (name "Net-(LED80-RES)") (class "Default")
      (node (ref "LED80") (pin "2") (pinfunction "RES_2") (pintype "passive"))
      (node (ref "U25") (pin "14") (pinfunction "3B_14") (pintype "passive"))
    )
    (net (code "177") (name "Net-(LED81-A)") (class "Default")
      (node (ref "LED81") (pin "1") (pinfunction "A_1") (pintype "passive"))
      (node (ref "R26") (pin "1") (pinfunction "1_1") (pintype "passive"))
    )
    (net (code "178") (name "Net-(LED82-RES)") (class "Default")
      (node (ref "LED82") (pin "2") (pinfunction "RES_2") (pintype "passive"))
      (node (ref "U20") (pin "13") (pinfunction "4B_13") (pintype "passive"))
    )
    (net (code "179") (name "Net-(LED83-RES)") (class "Default")
      (node (ref "LED83") (pin "2") (pinfunction "RES_2") (pintype "passive"))
      (node (ref "U21") (pin "13") (pinfunction "4B_13") (pintype "passive"))
    )
    (net (code "180") (name "Net-(LED84-RES)") (class "Default")
      (node (ref "LED84") (pin "2") (pinfunction "RES_2") (pintype "passive"))
      (node (ref "U22") (pin "13") (pinfunction "4B_13") (pintype "passive"))
    )
    (net (code "181") (name "Net-(LED85-RES)") (class "Default")
      (node (ref "LED85") (pin "2") (pinfunction "RES_2") (pintype "passive"))
      (node (ref "U23") (pin "13") (pinfunction "4B_13") (pintype "passive"))
    )
    (net (code "182") (name "Net-(LED86-RES)") (class "Default")
      (node (ref "LED86") (pin "2") (pinfunction "RES_2") (pintype "passive"))
      (node (ref "U24") (pin "13") (pinfunction "4B_13") (pintype "passive"))
    )
    (net (code "183") (name "Net-(LED87-RES)") (class "Default")
      (node (ref "LED87") (pin "2") (pinfunction "RES_2") (pintype "passive"))
      (node (ref "U25") (pin "13") (pinfunction "4B_13") (pintype "passive"))
    )
    (net (code "184") (name "Net-(LED88-RES)") (class "Default")
      (node (ref "LED88") (pin "2") (pinfunction "RES_2") (pintype "passive"))
      (node (ref "U20") (pin "12") (pinfunction "5B_12") (pintype "passive"))
    )
    (net (code "185") (name "Net-(LED89-RES)") (class "Default")
      (node (ref "LED89") (pin "2") (pinfunction "RES_2") (pintype "passive"))
      (node (ref "U11") (pin "16") (pinfunction "1B_16") (pintype "passive"))
    )
    (net (code "186") (name "Net-(LED90-RES)") (class "Default")
      (node (ref "LED90") (pin "2") (pinfunction "RES_2") (pintype "passive"))
      (node (ref "U22") (pin "12") (pinfunction "5B_12") (pintype "passive"))
    )
    (net (code "187") (name "Net-(LED91-RES)") (class "Default")
      (node (ref "LED91") (pin "2") (pinfunction "RES_2") (pintype "passive"))
      (node (ref "U23") (pin "12") (pinfunction "5B_12") (pintype "passive"))
    )
    (net (code "188") (name "Net-(LED92-RES)") (class "Default")
      (node (ref "LED92") (pin "2") (pinfunction "RES_2") (pintype "passive"))
      (node (ref "U24") (pin "12") (pinfunction "5B_12") (pintype "passive"))
    )
    (net (code "189") (name "Net-(LED93-RES)") (class "Default")
      (node (ref "LED93") (pin "2") (pinfunction "RES_2") (pintype "passive"))
      (node (ref "U25") (pin "12") (pinfunction "5B_12") (pintype "passive"))
    )
    (net (code "190") (name "Net-(LED94-RES)") (class "Default")
      (node (ref "LED94") (pin "2") (pinfunction "RES_2") (pintype "passive"))
      (node (ref "U20") (pin "11") (pinfunction "6B_11") (pintype "passive"))
    )
    (net (code "191") (name "Net-(LED95-RES)") (class "Default")
      (node (ref "LED95") (pin "2") (pinfunction "RES_2") (pintype "passive"))
      (node (ref "U11") (pin "15") (pinfunction "2B_15") (pintype "passive"))
    )
    (net (code "192") (name "Net-(LED96-RES)") (class "Default")
      (node (ref "LED96") (pin "2") (pinfunction "RES_2") (pintype "passive"))
      (node (ref "U22") (pin "11") (pinfunction "6B_11") (pintype "passive"))
    )
    (net (code "193") (name "Net-(LED97-RES)") (class "Default")
      (node (ref "LED97") (pin "2") (pinfunction "RES_2") (pintype "passive"))
      (node (ref "U23") (pin "11") (pinfunction "6B_11") (pintype "passive"))
    )
    (net (code "194") (name "Net-(LED98-RES)") (class "Default")
      (node (ref "LED98") (pin "2") (pinfunction "RES_2") (pintype "passive"))
      (node (ref "U24") (pin "11") (pinfunction "6B_11") (pintype "passive"))
    )
    (net (code "195") (name "Net-(LED99-RES)") (class "Default")
      (node (ref "LED99") (pin "2") (pinfunction "RES_2") (pintype "passive"))
      (node (ref "U25") (pin "11") (pinfunction "6B_11") (pintype "passive"))
    )
    (net (code "196") (name "Net-(LED100-A)") (class "Default")
      (node (ref "LED100") (pin "1") (pinfunction "A_1") (pintype "passive"))
      (node (ref "R27") (pin "1") (pinfunction "1_1") (pintype "passive"))
    )
    (net (code "197") (name "Net-(LED101-RES)") (class "Default")
      (node (ref "LED101") (pin "2") (pinfunction "RES_2") (pintype "passive"))
      (node (ref "U20") (pin "10") (pinfunction "7B_10") (pintype "passive"))
    )
    (net (code "198") (name "Net-(LED102-RES)") (class "Default")
      (node (ref "LED102") (pin "2") (pinfunction "RES_2") (pintype "passive"))
      (node (ref "U21") (pin "10") (pinfunction "7B_10") (pintype "passive"))
    )
    (net (code "199") (name "Net-(LED103-RES)") (class "Default")
      (node (ref "LED103") (pin "2") (pinfunction "RES_2") (pintype "passive"))
      (node (ref "U22") (pin "10") (pinfunction "7B_10") (pintype "passive"))
    )
    (net (code "200") (name "Net-(LED104-RES)") (class "Default")
      (node (ref "LED104") (pin "2") (pinfunction "RES_2") (pintype "passive"))
      (node (ref "U23") (pin "10") (pinfunction "7B_10") (pintype "passive"))
    )
    (net (code "201") (name "Net-(LED105-RES)") (class "Default")
      (node (ref "LED105") (pin "2") (pinfunction "RES_2") (pintype "passive"))
      (node (ref "U24") (pin "10") (pinfunction "7B_10") (pintype "passive"))
    )
    (net (code "202") (name "Net-(LED106-RES)") (class "Default")
      (node (ref "LED106") (pin "2") (pinfunction "RES_2") (pintype "passive"))
      (node (ref "U25") (pin "10") (pinfunction "7B_10") (pintype "passive"))
    )
    (net (code "203") (name "Net-(LED107-RES)") (class "Default")
      (node (ref "LED107") (pin "2") (pinfunction "RES_2") (pintype "passive"))
      (node (ref "U20") (pin "9") (pinfunction "8B_9") (pintype "passive"))
    )
    (net (code "204") (name "Net-(LED108-RES)") (class "Default")
      (node (ref "LED108") (pin "2") (pinfunction "RES_2") (pintype "passive"))
      (node (ref "U21") (pin "9") (pinfunction "8B_9") (pintype "passive"))
    )
    (net (code "205") (name "Net-(LED109-RES)") (class "Default")
      (node (ref "LED109") (pin "2") (pinfunction "RES_2") (pintype "passive"))
      (node (ref "U22") (pin "9") (pinfunction "8B_9") (pintype "passive"))
    )
    (net (code "206") (name "Net-(LED111-RES)") (class "Default")
      (node (ref "LED111") (pin "2") (pinfunction "RES_2") (pintype "passive"))
      (node (ref "U24") (pin "9") (pinfunction "8B_9") (pintype "passive"))
    )
    (net (code "207") (name "Net-(LED112-RES)") (class "Default")
      (node (ref "LED112") (pin "2") (pinfunction "RES_2") (pintype "passive"))
      (node (ref "U25") (pin "9") (pinfunction "8B_9") (pintype "passive"))
    )
    (net (code "208") (name "Net-(U2-Y1)") (class "Default")
      (node (ref "U2") (pin "18") (pinfunction "Y1_18") (pintype "tri_state"))
      (node (ref "U8") (pin "1") (pinfunction "1A_1") (pintype "passive"))
    )
    (net (code "209") (name "Net-(U2-Y2)") (class "Default")
      (node (ref "U2") (pin "17") (pinfunction "Y2_17") (pintype "tri_state"))
      (node (ref "U8") (pin "2") (pinfunction "2A_2") (pintype "passive"))
    )
    (net (code "210") (name "Net-(U2-Y3)") (class "Default")
      (node (ref "U2") (pin "16") (pinfunction "Y3_16") (pintype "tri_state"))
      (node (ref "U8") (pin "3") (pinfunction "3A_3") (pintype "passive"))
    )
    (net (code "211") (name "Net-(U2-Y4)") (class "Default")
      (node (ref "U2") (pin "15") (pinfunction "Y4_15") (pintype "tri_state"))
      (node (ref "U8") (pin "4") (pinfunction "4A_4") (pintype "passive"))
    )
    (net (code "212") (name "Net-(U2-Y5)") (class "Default")
      (node (ref "U2") (pin "14") (pinfunction "Y5_14") (pintype "tri_state"))
      (node (ref "U8") (pin "5") (pinfunction "5A_5") (pintype "passive"))
    )
    (net (code "213") (name "Net-(U2-Y6)") (class "Default")
      (node (ref "U2") (pin "13") (pinfunction "Y6_13") (pintype "tri_state"))
      (node (ref "U8") (pin "6") (pinfunction "6A_6") (pintype "passive"))
    )
    (net (code "214") (name "Net-(U2-Y7)") (class "Default")
      (node (ref "U2") (pin "12") (pinfunction "Y7_12") (pintype "tri_state"))
      (node (ref "U8") (pin "7") (pinfunction "7A_7") (pintype "passive"))
    )
    (net (code "215") (name "Net-(U2-Y8)") (class "Default")
      (node (ref "U2") (pin "11") (pinfunction "Y8_11") (pintype "tri_state"))
      (node (ref "U8") (pin "8") (pinfunction "8A_8") (pintype "passive"))
    )
    (net (code "216") (name "Net-(U3-Y1)") (class "Default")
      (node (ref "U3") (pin "18") (pinfunction "Y1_18") (pintype "tri_state"))
      (node (ref "U9") (pin "1") (pinfunction "1A_1") (pintype "passive"))
    )
    (net (code "217") (name "Net-(U3-Y2)") (class "Default")
      (node (ref "U3") (pin "17") (pinfunction "Y2_17") (pintype "tri_state"))
      (node (ref "U9") (pin "2") (pinfunction "2A_2") (pintype "passive"))
    )
    (net (code "218") (name "Net-(U3-Y3)") (class "Default")
      (node (ref "U3") (pin "16") (pinfunction "Y3_16") (pintype "tri_state"))
      (node (ref "U9") (pin "3") (pinfunction "3A_3") (pintype "passive"))
    )
    (net (code "219") (name "Net-(U3-Y4)") (class "Default")
      (node (ref "U3") (pin "15") (pinfunction "Y4_15") (pintype "tri_state"))
      (node (ref "U9") (pin "4") (pinfunction "4A_4") (pintype "passive"))
    )
    (net (code "220") (name "Net-(U3-Y5)") (class "Default")
      (node (ref "U3") (pin "14") (pinfunction "Y5_14") (pintype "tri_state"))
      (node (ref "U9") (pin "5") (pinfunction "5A_5") (pintype "passive"))
    )
    (net (code "221") (name "Net-(U3-Y6)") (class "Default")
      (node (ref "U3") (pin "13") (pinfunction "Y6_13") (pintype "tri_state"))
      (node (ref "U9") (pin "6") (pinfunction "6A_6") (pintype "passive"))
    )
    (net (code "222") (name "Net-(U3-Y7)") (class "Default")
      (node (ref "U3") (pin "12") (pinfunction "Y7_12") (pintype "tri_state"))
      (node (ref "U9") (pin "7") (pinfunction "7A_7") (pintype "passive"))
    )
    (net (code "223") (name "Net-(U3-Y8)") (class "Default")
      (node (ref "U3") (pin "11") (pinfunction "Y8_11") (pintype "tri_state"))
      (node (ref "U9") (pin "8") (pinfunction "8A_8") (pintype "passive"))
    )
    (net (code "224") (name "Net-(U10-1A)") (class "Default")
      (node (ref "U10") (pin "1") (pinfunction "1A_1") (pintype "passive"))
      (node (ref "U4") (pin "18") (pinfunction "Y1_18") (pintype "tri_state"))
    )
    (net (code "225") (name "Net-(U10-2A)") (class "Default")
      (node (ref "U10") (pin "2") (pinfunction "2A_2") (pintype "passive"))
      (node (ref "U4") (pin "17") (pinfunction "Y2_17") (pintype "tri_state"))
    )
    (net (code "226") (name "Net-(U10-3A)") (class "Default")
      (node (ref "U10") (pin "3") (pinfunction "3A_3") (pintype "passive"))
      (node (ref "U4") (pin "16") (pinfunction "Y3_16") (pintype "tri_state"))
    )
    (net (code "227") (name "Net-(U10-4A)") (class "Default")
      (node (ref "U10") (pin "4") (pinfunction "4A_4") (pintype "passive"))
      (node (ref "U4") (pin "15") (pinfunction "Y4_15") (pintype "tri_state"))
    )
    (net (code "228") (name "Net-(U10-5A)") (class "Default")
      (node (ref "U10") (pin "5") (pinfunction "5A_5") (pintype "passive"))
      (node (ref "U4") (pin "14") (pinfunction "Y5_14") (pintype "tri_state"))
    )
    (net (code "229") (name "Net-(U10-6A)") (class "Default")
      (node (ref "U10") (pin "6") (pinfunction "6A_6") (pintype "passive"))
      (node (ref "U4") (pin "13") (pinfunction "Y6_13") (pintype "tri_state"))
    )
    (net (code "230") (name "Net-(U10-7A)") (class "Default")
      (node (ref "U10") (pin "7") (pinfunction "7A_7") (pintype "passive"))
      (node (ref "U4") (pin "12") (pinfunction "Y7_12") (pintype "tri_state"))
    )
    (net (code "231") (name "Net-(U10-8A)") (class "Default")
      (node (ref "U10") (pin "8") (pinfunction "8A_8") (pintype "passive"))
      (node (ref "U4") (pin "11") (pinfunction "Y8_11") (pintype "tri_state"))
    )
    (net (code "232") (name "Net-(U11-1A)") (class "Default")
      (node (ref "U11") (pin "1") (pinfunction "1A_1") (pintype "passive"))
      (node (ref "U5") (pin "18") (pinfunction "Y1_18") (pintype "tri_state"))
    )
    (net (code "233") (name "Net-(U11-2A)") (class "Default")
      (node (ref "U11") (pin "2") (pinfunction "2A_2") (pintype "passive"))
      (node (ref "U5") (pin "17") (pinfunction "Y2_17") (pintype "tri_state"))
    )
    (net (code "234") (name "Net-(U11-3A)") (class "Default")
      (node (ref "U11") (pin "3") (pinfunction "3A_3") (pintype "passive"))
      (node (ref "U5") (pin "16") (pinfunction "Y3_16") (pintype "tri_state"))
    )
    (net (code "235") (name "Net-(U11-4A)") (class "Default")
      (node (ref "U11") (pin "4") (pinfunction "4A_4") (pintype "passive"))
      (node (ref "U5") (pin "15") (pinfunction "Y4_15") (pintype "tri_state"))
    )
    (net (code "236") (name "Net-(U11-5A)") (class "Default")
      (node (ref "U11") (pin "5") (pinfunction "5A_5") (pintype "passive"))
      (node (ref "U5") (pin "14") (pinfunction "Y5_14") (pintype "tri_state"))
    )
    (net (code "237") (name "Net-(U11-6A)") (class "Default")
      (node (ref "U11") (pin "6") (pinfunction "6A_6") (pintype "passive"))
      (node (ref "U5") (pin "13") (pinfunction "Y6_13") (pintype "tri_state"))
    )
    (net (code "238") (name "Net-(U11-7A)") (class "Default")
      (node (ref "U11") (pin "7") (pinfunction "7A_7") (pintype "passive"))
      (node (ref "U5") (pin "12") (pinfunction "Y7_12") (pintype "tri_state"))
    )
    (net (code "239") (name "Net-(U11-8A)") (class "Default")
      (node (ref "U11") (pin "8") (pinfunction "8A_8") (pintype "passive"))
      (node (ref "U5") (pin "11") (pinfunction "Y8_11") (pintype "tri_state"))
    )
    (net (code "240") (name "Net-(U12-1A)") (class "Default")
      (node (ref "U12") (pin "1") (pinfunction "1A_1") (pintype "passive"))
      (node (ref "U6") (pin "18") (pinfunction "Y1_18") (pintype "tri_state"))
    )
    (net (code "241") (name "Net-(U12-2A)") (class "Default")
      (node (ref "U12") (pin "2") (pinfunction "2A_2") (pintype "passive"))
      (node (ref "U6") (pin "17") (pinfunction "Y2_17") (pintype "tri_state"))
    )
    (net (code "242") (name "Net-(U12-3A)") (class "Default")
      (node (ref "U12") (pin "3") (pinfunction "3A_3") (pintype "passive"))
      (node (ref "U6") (pin "16") (pinfunction "Y3_16") (pintype "tri_state"))
    )
    (net (code "243") (name "Net-(U12-4A)") (class "Default")
      (node (ref "U12") (pin "4") (pinfunction "4A_4") (pintype "passive"))
      (node (ref "U6") (pin "15") (pinfunction "Y4_15") (pintype "tri_state"))
    )
    (net (code "244") (name "Net-(U12-5A)") (class "Default")
      (node (ref "U12") (pin "5") (pinfunction "5A_5") (pintype "passive"))
      (node (ref "U6") (pin "14") (pinfunction "Y5_14") (pintype "tri_state"))
    )
    (net (code "245") (name "Net-(U12-6A)") (class "Default")
      (node (ref "U12") (pin "6") (pinfunction "6A_6") (pintype "passive"))
      (node (ref "U6") (pin "13") (pinfunction "Y6_13") (pintype "tri_state"))
    )
    (net (code "246") (name "Net-(U12-7A)") (class "Default")
      (node (ref "U12") (pin "7") (pinfunction "7A_7") (pintype "passive"))
      (node (ref "U6") (pin "12") (pinfunction "Y7_12") (pintype "tri_state"))
    )
    (net (code "247") (name "Net-(U12-8A)") (class "Default")
      (node (ref "U12") (pin "8") (pinfunction "8A_8") (pintype "passive"))
      (node (ref "U6") (pin "11") (pinfunction "Y8_11") (pintype "tri_state"))
    )
    (net (code "248") (name "Net-(U13-1A)") (class "Default")
      (node (ref "U13") (pin "1") (pinfunction "1A_1") (pintype "passive"))
      (node (ref "U7") (pin "18") (pinfunction "Y1_18") (pintype "tri_state"))
    )
    (net (code "249") (name "Net-(U13-2A)") (class "Default")
      (node (ref "U13") (pin "2") (pinfunction "2A_2") (pintype "passive"))
      (node (ref "U7") (pin "17") (pinfunction "Y2_17") (pintype "tri_state"))
    )
    (net (code "250") (name "Net-(U13-3A)") (class "Default")
      (node (ref "U13") (pin "3") (pinfunction "3A_3") (pintype "passive"))
      (node (ref "U7") (pin "16") (pinfunction "Y3_16") (pintype "tri_state"))
    )
    (net (code "251") (name "Net-(U13-4A)") (class "Default")
      (node (ref "U13") (pin "4") (pinfunction "4A_4") (pintype "passive"))
      (node (ref "U7") (pin "15") (pinfunction "Y4_15") (pintype "tri_state"))
    )
    (net (code "252") (name "Net-(U13-5A)") (class "Default")
      (node (ref "U13") (pin "5") (pinfunction "5A_5") (pintype "passive"))
      (node (ref "U7") (pin "14") (pinfunction "Y5_14") (pintype "tri_state"))
    )
    (net (code "253") (name "Net-(U13-6A)") (class "Default")
      (node (ref "U13") (pin "6") (pinfunction "6A_6") (pintype "passive"))
      (node (ref "U7") (pin "13") (pinfunction "Y6_13") (pintype "tri_state"))
    )
    (net (code "254") (name "Net-(U13-7A)") (class "Default")
      (node (ref "U13") (pin "7") (pinfunction "7A_7") (pintype "passive"))
      (node (ref "U7") (pin "12") (pinfunction "Y7_12") (pintype "tri_state"))
    )
    (net (code "255") (name "Net-(U13-8A)") (class "Default")
      (node (ref "U13") (pin "8") (pinfunction "8A_8") (pintype "passive"))
      (node (ref "U7") (pin "11") (pinfunction "Y8_11") (pintype "tri_state"))
    )
    (net (code "256") (name "Net-(U14-Y1)") (class "Default")
      (node (ref "U14") (pin "18") (pinfunction "Y1_18") (pintype "tri_state"))
      (node (ref "U20") (pin "1") (pinfunction "1A_1") (pintype "passive"))
    )
    (net (code "257") (name "Net-(U14-Y2)") (class "Default")
      (node (ref "U14") (pin "17") (pinfunction "Y2_17") (pintype "tri_state"))
      (node (ref "U20") (pin "2") (pinfunction "2A_2") (pintype "passive"))
    )
    (net (code "258") (name "Net-(U14-Y3)") (class "Default")
      (node (ref "U14") (pin "16") (pinfunction "Y3_16") (pintype "tri_state"))
      (node (ref "U20") (pin "3") (pinfunction "3A_3") (pintype "passive"))
    )
    (net (code "259") (name "Net-(U14-Y4)") (class "Default")
      (node (ref "U14") (pin "15") (pinfunction "Y4_15") (pintype "tri_state"))
      (node (ref "U20") (pin "4") (pinfunction "4A_4") (pintype "passive"))
    )
    (net (code "260") (name "Net-(U14-Y5)") (class "Default")
      (node (ref "U14") (pin "14") (pinfunction "Y5_14") (pintype "tri_state"))
      (node (ref "U20") (pin "5") (pinfunction "5A_5") (pintype "passive"))
    )
    (net (code "261") (name "Net-(U14-Y6)") (class "Default")
      (node (ref "U14") (pin "13") (pinfunction "Y6_13") (pintype "tri_state"))
      (node (ref "U20") (pin "6") (pinfunction "6A_6") (pintype "passive"))
    )
    (net (code "262") (name "Net-(U14-Y7)") (class "Default")
      (node (ref "U14") (pin "12") (pinfunction "Y7_12") (pintype "tri_state"))
      (node (ref "U20") (pin "7") (pinfunction "7A_7") (pintype "passive"))
    )
    (net (code "263") (name "Net-(U14-Y8)") (class "Default")
      (node (ref "U14") (pin "11") (pinfunction "Y8_11") (pintype "tri_state"))
      (node (ref "U20") (pin "8") (pinfunction "8A_8") (pintype "passive"))
    )
    (net (code "264") (name "Net-(U15-Y1)") (class "Default")
      (node (ref "U15") (pin "18") (pinfunction "Y1_18") (pintype "tri_state"))
      (node (ref "U21") (pin "1") (pinfunction "1A_1") (pintype "passive"))
    )
    (net (code "265") (name "Net-(U15-Y2)") (class "Default")
      (node (ref "U15") (pin "17") (pinfunction "Y2_17") (pintype "tri_state"))
      (node (ref "U21") (pin "2") (pinfunction "2A_2") (pintype "passive"))
    )
    (net (code "266") (name "Net-(U15-Y3)") (class "Default")
      (node (ref "U15") (pin "16") (pinfunction "Y3_16") (pintype "tri_state"))
      (node (ref "U21") (pin "3") (pinfunction "3A_3") (pintype "passive"))
    )
    (net (code "267") (name "Net-(U15-Y4)") (class "Default")
      (node (ref "U15") (pin "15") (pinfunction "Y4_15") (pintype "tri_state"))
      (node (ref "U21") (pin "4") (pinfunction "4A_4") (pintype "passive"))
    )
    (net (code "268") (name "Net-(U15-Y5)") (class "Default")
      (node (ref "U15") (pin "14") (pinfunction "Y5_14") (pintype "tri_state"))
      (node (ref "U21") (pin "5") (pinfunction "5A_5") (pintype "passive"))
    )
    (net (code "269") (name "Net-(U15-Y6)") (class "Default")
      (node (ref "U15") (pin "13") (pinfunction "Y6_13") (pintype "tri_state"))
      (node (ref "U21") (pin "6") (pinfunction "6A_6") (pintype "passive"))
    )
    (net (code "270") (name "Net-(U15-Y7)") (class "Default")
      (node (ref "U15") (pin "12") (pinfunction "Y7_12") (pintype "tri_state"))
      (node (ref "U21") (pin "7") (pinfunction "7A_7") (pintype "passive"))
    )
    (net (code "271") (name "Net-(U15-Y8)") (class "Default")
      (node (ref "U15") (pin "11") (pinfunction "Y8_11") (pintype "tri_state"))
      (node (ref "U21") (pin "8") (pinfunction "8A_8") (pintype "passive"))
    )
    (net (code "272") (name "Net-(U16-Y1)") (class "Default")
      (node (ref "U16") (pin "18") (pinfunction "Y1_18") (pintype "tri_state"))
      (node (ref "U22") (pin "1") (pinfunction "1A_1") (pintype "passive"))
    )
    (net (code "273") (name "Net-(U16-Y2)") (class "Default")
      (node (ref "U16") (pin "17") (pinfunction "Y2_17") (pintype "tri_state"))
      (node (ref "U22") (pin "2") (pinfunction "2A_2") (pintype "passive"))
    )
    (net (code "274") (name "Net-(U16-Y3)") (class "Default")
      (node (ref "U16") (pin "16") (pinfunction "Y3_16") (pintype "tri_state"))
      (node (ref "U22") (pin "3") (pinfunction "3A_3") (pintype "passive"))
    )
    (net (code "275") (name "Net-(U16-Y4)") (class "Default")
      (node (ref "U16") (pin "15") (pinfunction "Y4_15") (pintype "tri_state"))
      (node (ref "U22") (pin "4") (pinfunction "4A_4") (pintype "passive"))
    )
    (net (code "276") (name "Net-(U16-Y5)") (class "Default")
      (node (ref "U16") (pin "14") (pinfunction "Y5_14") (pintype "tri_state"))
      (node (ref "U22") (pin "5") (pinfunction "5A_5") (pintype "passive"))
    )
    (net (code "277") (name "Net-(U16-Y6)") (class "Default")
      (node (ref "U16") (pin "13") (pinfunction "Y6_13") (pintype "tri_state"))
      (node (ref "U22") (pin "6") (pinfunction "6A_6") (pintype "passive"))
    )
    (net (code "278") (name "Net-(U16-Y7)") (class "Default")
      (node (ref "U16") (pin "12") (pinfunction "Y7_12") (pintype "tri_state"))
      (node (ref "U22") (pin "7") (pinfunction "7A_7") (pintype "passive"))
    )
    (net (code "279") (name "Net-(U16-Y8)") (class "Default")
      (node (ref "U16") (pin "11") (pinfunction "Y8_11") (pintype "tri_state"))
      (node (ref "U22") (pin "8") (pinfunction "8A_8") (pintype "passive"))
    )
    (net (code "280") (name "Net-(U17-Y1)") (class "Default")
      (node (ref "U17") (pin "18") (pinfunction "Y1_18") (pintype "tri_state"))
      (node (ref "U23") (pin "1") (pinfunction "1A_1") (pintype "passive"))
    )
    (net (code "281") (name "Net-(U17-Y2)") (class "Default")
      (node (ref "U17") (pin "17") (pinfunction "Y2_17") (pintype "tri_state"))
      (node (ref "U23") (pin "2") (pinfunction "2A_2") (pintype "passive"))
    )
    (net (code "282") (name "Net-(U17-Y3)") (class "Default")
      (node (ref "U17") (pin "16") (pinfunction "Y3_16") (pintype "tri_state"))
      (node (ref "U23") (pin "3") (pinfunction "3A_3") (pintype "passive"))
    )
    (net (code "283") (name "Net-(U17-Y4)") (class "Default")
      (node (ref "U17") (pin "15") (pinfunction "Y4_15") (pintype "tri_state"))
      (node (ref "U23") (pin "4") (pinfunction "4A_4") (pintype "passive"))
    )
    (net (code "284") (name "Net-(U17-Y5)") (class "Default")
      (node (ref "U17") (pin "14") (pinfunction "Y5_14") (pintype "tri_state"))
      (node (ref "U23") (pin "5") (pinfunction "5A_5") (pintype "passive"))
    )
    (net (code "285") (name "Net-(U17-Y6)") (class "Default")
      (node (ref "U17") (pin "13") (pinfunction "Y6_13") (pintype "tri_state"))
      (node (ref "U23") (pin "6") (pinfunction "6A_6") (pintype "passive"))
    )
    (net (code "286") (name "Net-(U17-Y7)") (class "Default")
      (node (ref "U17") (pin "12") (pinfunction "Y7_12") (pintype "tri_state"))
      (node (ref "U23") (pin "7") (pinfunction "7A_7") (pintype "passive"))
    )
    (net (code "287") (name "Net-(U17-Y8)") (class "Default")
      (node (ref "U17") (pin "11") (pinfunction "Y8_11") (pintype "tri_state"))
      (node (ref "U23") (pin "8") (pinfunction "8A_8") (pintype "passive"))
    )
    (net (code "288") (name "Net-(U18-A1)") (class "Default")
      (node (ref "J35") (pin "1") (pinfunction "1_1") (pintype "passive"))
      (node (ref "U18") (pin "2") (pinfunction "A1_2") (pintype "input"))
    )
    (net (code "289") (name "Net-(U18-A2)") (class "Default")
      (node (ref "J35") (pin "2") (pinfunction "2_2") (pintype "passive"))
      (node (ref "U18") (pin "3") (pinfunction "A2_3") (pintype "input"))
    )
    (net (code "290") (name "Net-(U18-A3)") (class "Default")
      (node (ref "J35") (pin "3") (pinfunction "3_3") (pintype "passive"))
      (node (ref "U18") (pin "4") (pinfunction "A3_4") (pintype "input"))
    )
    (net (code "291") (name "Net-(U18-A4)") (class "Default")
      (node (ref "J35") (pin "4") (pinfunction "4_4") (pintype "passive"))
      (node (ref "U18") (pin "5") (pinfunction "A4_5") (pintype "input"))
    )
    (net (code "292") (name "Net-(U18-A5)") (class "Default")
      (node (ref "J35") (pin "5") (pinfunction "5_5") (pintype "passive"))
      (node (ref "U18") (pin "6") (pinfunction "A5_6") (pintype "input"))
    )
    (net (code "293") (name "Net-(U18-A6)") (class "Default")
      (node (ref "J35") (pin "6") (pinfunction "6_6") (pintype "passive"))
      (node (ref "U18") (pin "7") (pinfunction "A6_7") (pintype "input"))
    )
    (net (code "294") (name "Net-(U18-A7)") (class "Default")
      (node (ref "J35") (pin "7") (pinfunction "7_7") (pintype "passive"))
      (node (ref "U18") (pin "8") (pinfunction "A7_8") (pintype "input"))
    )
    (net (code "295") (name "Net-(U18-A8)") (class "Default")
      (node (ref "J35") (pin "8") (pinfunction "8_8") (pintype "passive"))
      (node (ref "U18") (pin "9") (pinfunction "A8_9") (pintype "input"))
    )
    (net (code "296") (name "Net-(U18-Y1)") (class "Default")
      (node (ref "U18") (pin "18") (pinfunction "Y1_18") (pintype "tri_state"))
      (node (ref "U24") (pin "1") (pinfunction "1A_1") (pintype "passive"))
    )
    (net (code "297") (name "Net-(U18-Y2)") (class "Default")
      (node (ref "U18") (pin "17") (pinfunction "Y2_17") (pintype "tri_state"))
      (node (ref "U24") (pin "2") (pinfunction "2A_2") (pintype "passive"))
    )
    (net (code "298") (name "Net-(U18-Y3)") (class "Default")
      (node (ref "U18") (pin "16") (pinfunction "Y3_16") (pintype "tri_state"))
      (node (ref "U24") (pin "3") (pinfunction "3A_3") (pintype "passive"))
    )
    (net (code "299") (name "Net-(U18-Y4)") (class "Default")
      (node (ref "U18") (pin "15") (pinfunction "Y4_15") (pintype "tri_state"))
      (node (ref "U24") (pin "4") (pinfunction "4A_4") (pintype "passive"))
    )
    (net (code "300") (name "Net-(U18-Y5)") (class "Default")
      (node (ref "U18") (pin "14") (pinfunction "Y5_14") (pintype "tri_state"))
      (node (ref "U24") (pin "5") (pinfunction "5A_5") (pintype "passive"))
    )
    (net (code "301") (name "Net-(U18-Y6)") (class "Default")
      (node (ref "U18") (pin "13") (pinfunction "Y6_13") (pintype "tri_state"))
      (node (ref "U24") (pin "6") (pinfunction "6A_6") (pintype "passive"))
    )
    (net (code "302") (name "Net-(U18-Y7)") (class "Default")
      (node (ref "U18") (pin "12") (pinfunction "Y7_12") (pintype "tri_state"))
      (node (ref "U24") (pin "7") (pinfunction "7A_7") (pintype "passive"))
    )
    (net (code "303") (name "Net-(U18-Y8)") (class "Default")
      (node (ref "U18") (pin "11") (pinfunction "Y8_11") (pintype "tri_state"))
      (node (ref "U24") (pin "8") (pinfunction "8A_8") (pintype "passive"))
    )
    (net (code "304") (name "Net-(U19-A1)") (class "Default")
      (node (ref "J36") (pin "1") (pinfunction "1_1") (pintype "passive"))
      (node (ref "U19") (pin "2") (pinfunction "A1_2") (pintype "input"))
    )
    (net (code "305") (name "Net-(U19-A2)") (class "Default")
      (node (ref "J36") (pin "2") (pinfunction "2_2") (pintype "passive"))
      (node (ref "U19") (pin "3") (pinfunction "A2_3") (pintype "input"))
    )
    (net (code "306") (name "Net-(U19-A3)") (class "Default")
      (node (ref "J36") (pin "3") (pinfunction "3_3") (pintype "passive"))
      (node (ref "U19") (pin "4") (pinfunction "A3_4") (pintype "input"))
    )
    (net (code "307") (name "Net-(U19-A4)") (class "Default")
      (node (ref "J36") (pin "4") (pinfunction "4_4") (pintype "passive"))
      (node (ref "U19") (pin "5") (pinfunction "A4_5") (pintype "input"))
    )
    (net (code "308") (name "Net-(U19-A5)") (class "Default")
      (node (ref "J36") (pin "5") (pinfunction "5_5") (pintype "passive"))
      (node (ref "U19") (pin "6") (pinfunction "A5_6") (pintype "input"))
    )
    (net (code "309") (name "Net-(U19-A6)") (class "Default")
      (node (ref "J36") (pin "6") (pinfunction "6_6") (pintype "passive"))
      (node (ref "U19") (pin "7") (pinfunction "A6_7") (pintype "input"))
    )
    (net (code "310") (name "Net-(U19-A7)") (class "Default")
      (node (ref "J36") (pin "7") (pinfunction "7_7") (pintype "passive"))
      (node (ref "U19") (pin "8") (pinfunction "A7_8") (pintype "input"))
    )
    (net (code "311") (name "Net-(U19-A8)") (class "Default")
      (node (ref "J36") (pin "8") (pinfunction "8_8") (pintype "passive"))
      (node (ref "U19") (pin "9") (pinfunction "A8_9") (pintype "input"))
    )
    (net (code "312") (name "Net-(U19-Y1)") (class "Default")
      (node (ref "U19") (pin "18") (pinfunction "Y1_18") (pintype "tri_state"))
      (node (ref "U25") (pin "1") (pinfunction "1A_1") (pintype "passive"))
    )
    (net (code "313") (name "Net-(U19-Y2)") (class "Default")
      (node (ref "U19") (pin "17") (pinfunction "Y2_17") (pintype "tri_state"))
      (node (ref "U25") (pin "2") (pinfunction "2A_2") (pintype "passive"))
    )
    (net (code "314") (name "Net-(U19-Y3)") (class "Default")
      (node (ref "U19") (pin "16") (pinfunction "Y3_16") (pintype "tri_state"))
      (node (ref "U25") (pin "3") (pinfunction "3A_3") (pintype "passive"))
    )
    (net (code "315") (name "Net-(U19-Y4)") (class "Default")
      (node (ref "U19") (pin "15") (pinfunction "Y4_15") (pintype "tri_state"))
      (node (ref "U25") (pin "4") (pinfunction "4A_4") (pintype "passive"))
    )
    (net (code "316") (name "Net-(U19-Y5)") (class "Default")
      (node (ref "U19") (pin "14") (pinfunction "Y5_14") (pintype "tri_state"))
      (node (ref "U25") (pin "5") (pinfunction "5A_5") (pintype "passive"))
    )
    (net (code "317") (name "Net-(U19-Y6)") (class "Default")
      (node (ref "U19") (pin "13") (pinfunction "Y6_13") (pintype "tri_state"))
      (node (ref "U25") (pin "6") (pinfunction "6A_6") (pintype "passive"))
    )
    (net (code "318") (name "Net-(U19-Y7)") (class "Default")
      (node (ref "U19") (pin "12") (pinfunction "Y7_12") (pintype "tri_state"))
      (node (ref "U25") (pin "7") (pinfunction "7A_7") (pintype "passive"))
    )
    (net (code "319") (name "Net-(U19-Y8)") (class "Default")
      (node (ref "U19") (pin "11") (pinfunction "Y8_11") (pintype "tri_state"))
      (node (ref "U25") (pin "8") (pinfunction "8A_8") (pintype "passive"))
    )
    (net (code "320") (name "unconnected-(U17-A8-Pad9)") (class "Default")
      (node (ref "U17") (pin "9") (pinfunction "A8_9") (pintype "input+no_connect"))
    )
    (net (code "321") (name "unconnected-(U19-GND-Pad10)") (class "Default")
      (node (ref "U19") (pin "10") (pinfunction "GND_10") (pintype "power_in"))
    )
    (net (code "322") (name "unconnected-(U23-8B-Pad9)") (class "Default")
      (node (ref "U23") (pin "9") (pinfunction "8B_9") (pintype "passive+no_connect"))
    )
  )
)
